# SmartCellPrototype.net
KiCad netlist of a schematic drawn in EAGLE
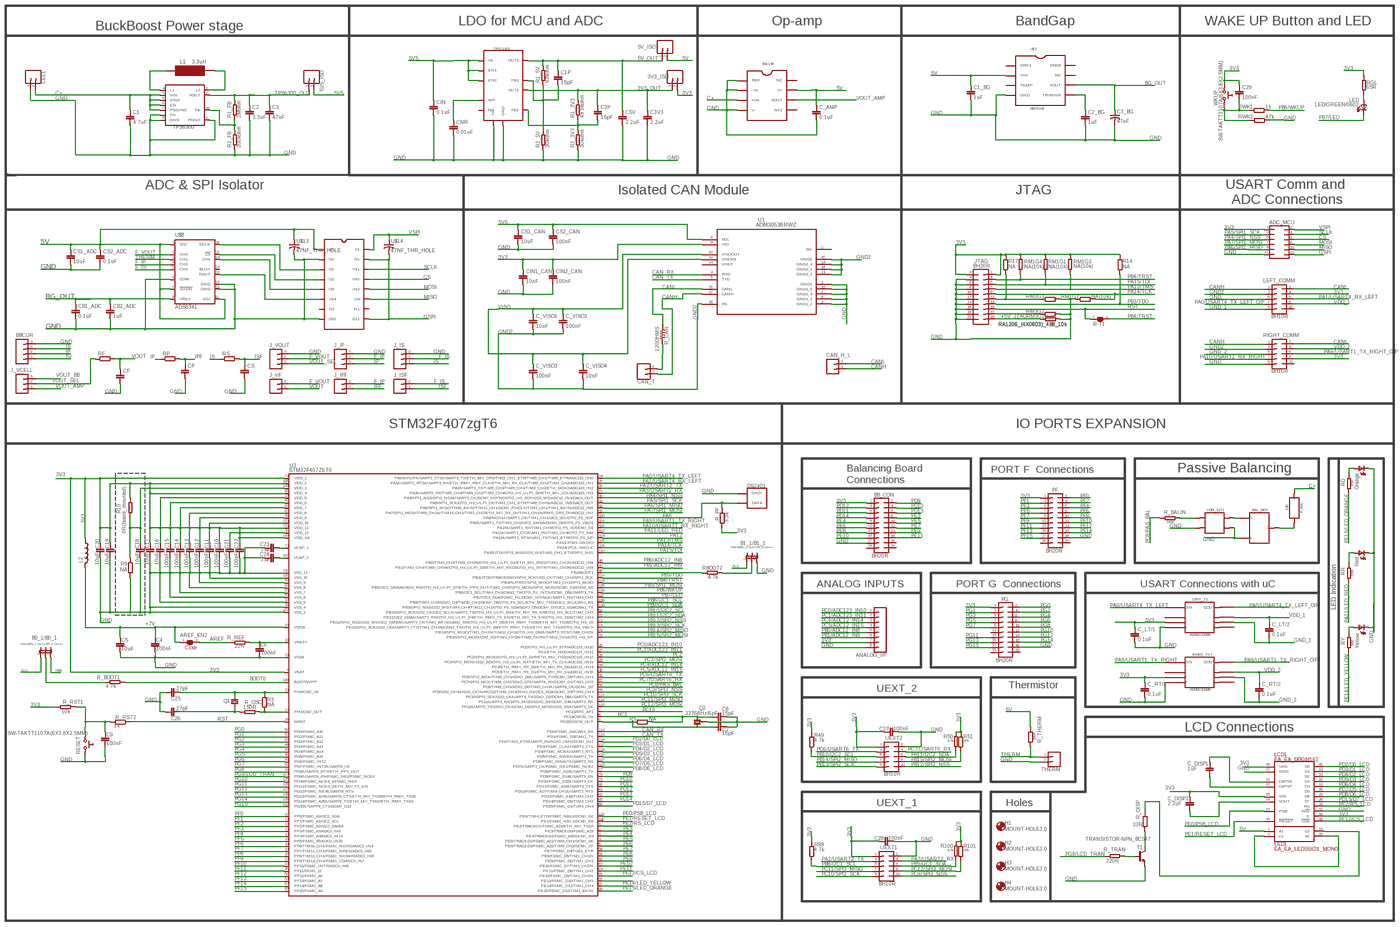
[diagram p0: schematic, sheet 1, overview]
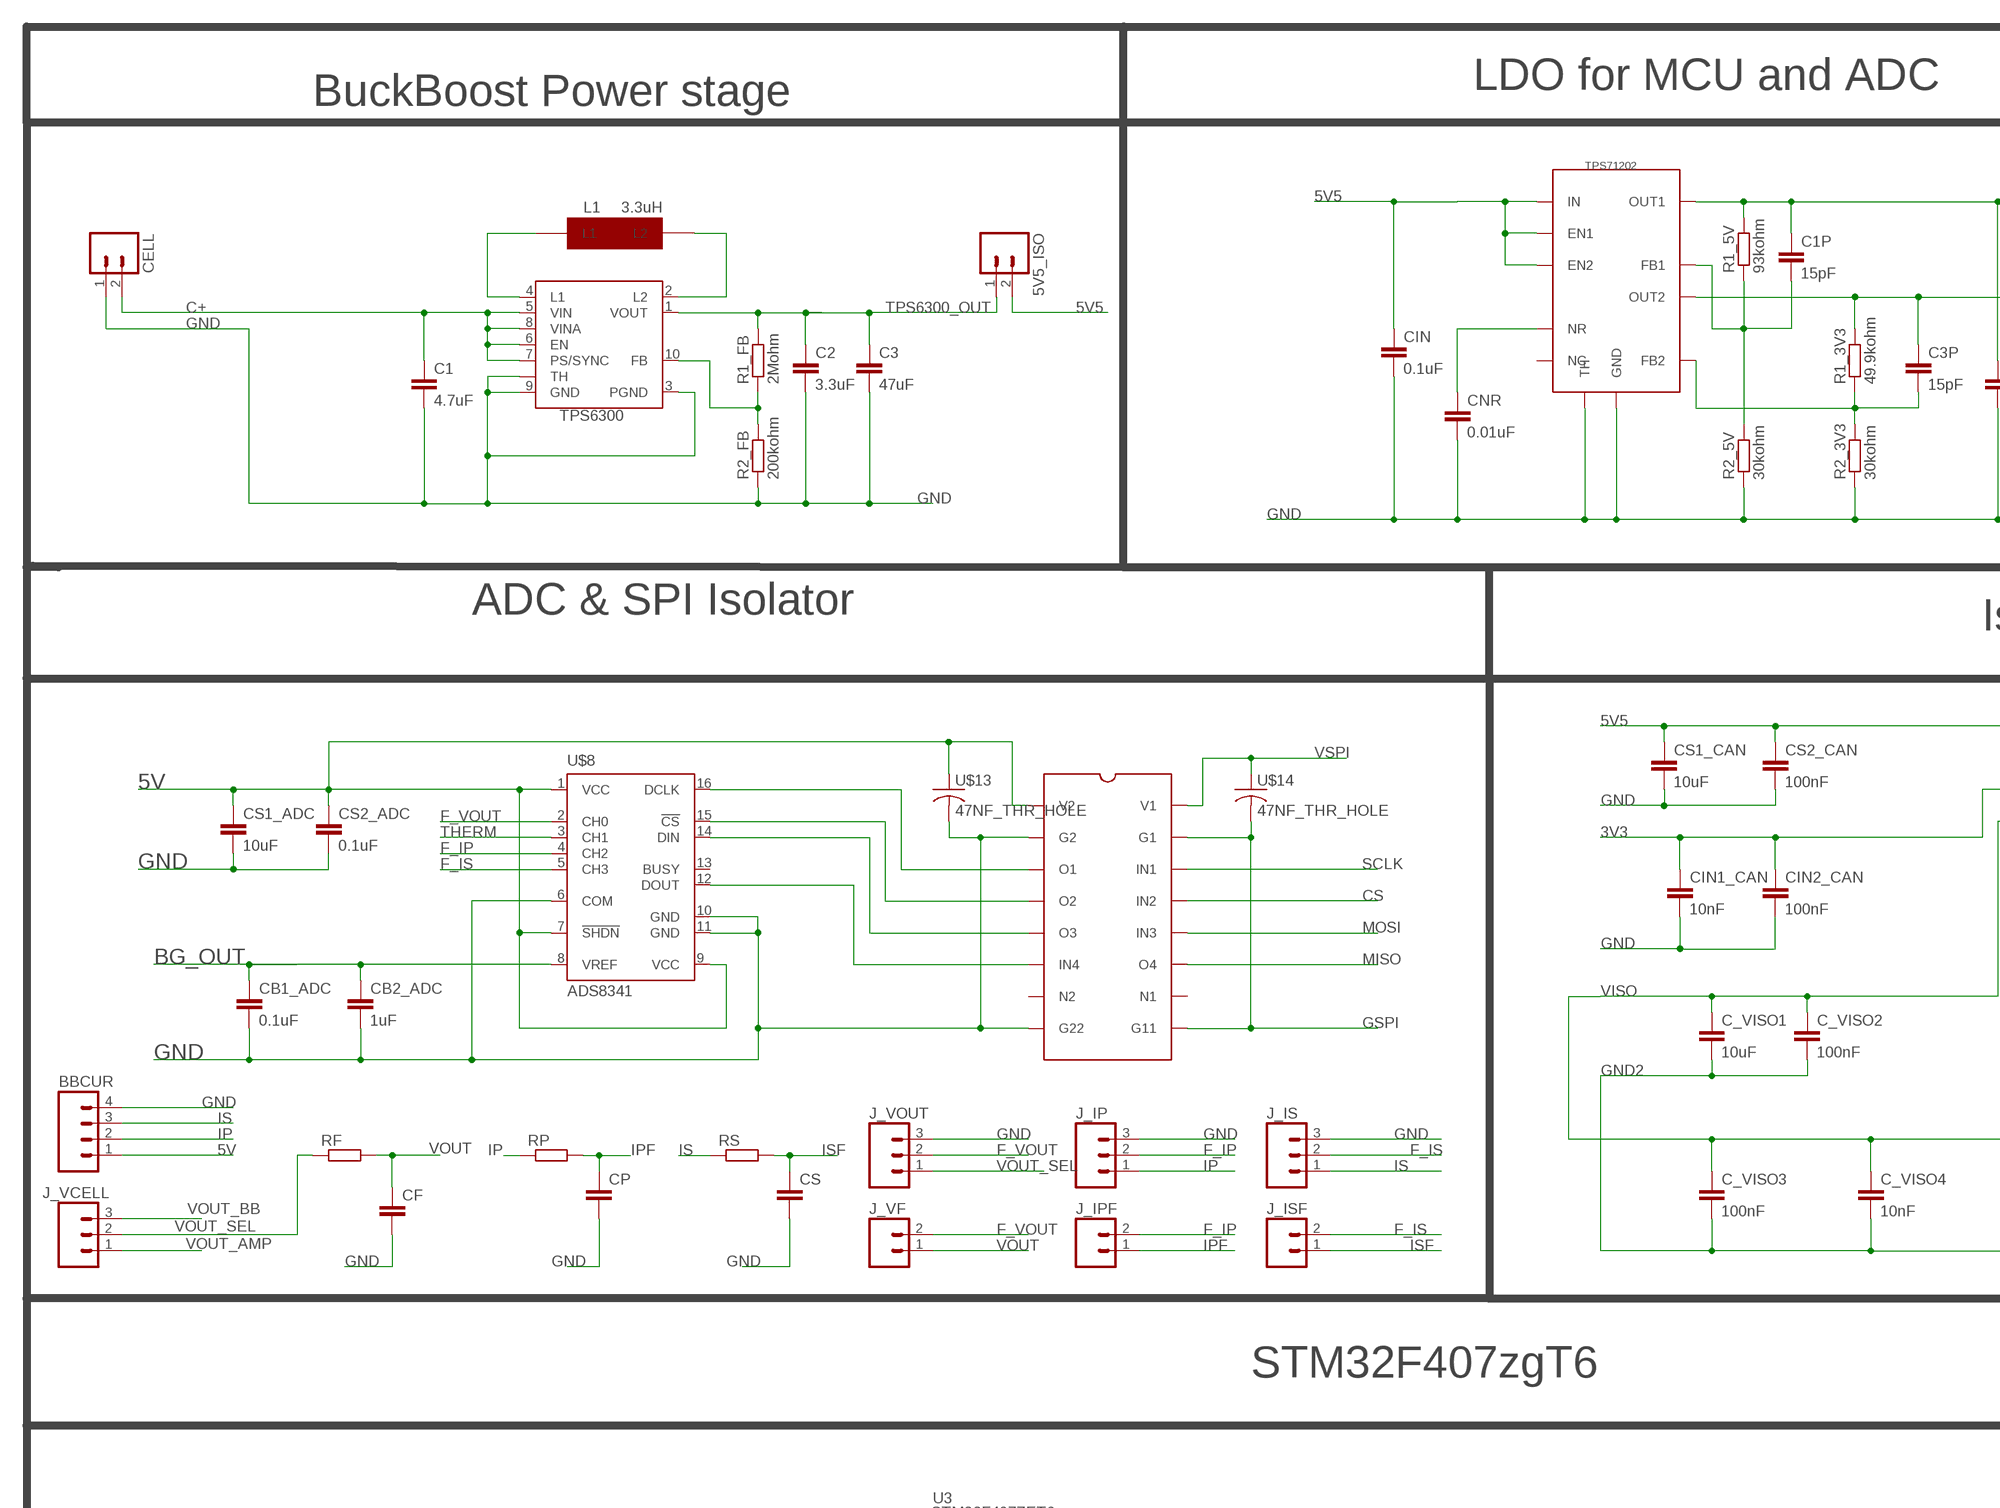
[diagram p1: schematic, sheet 1, part 1 of 4]
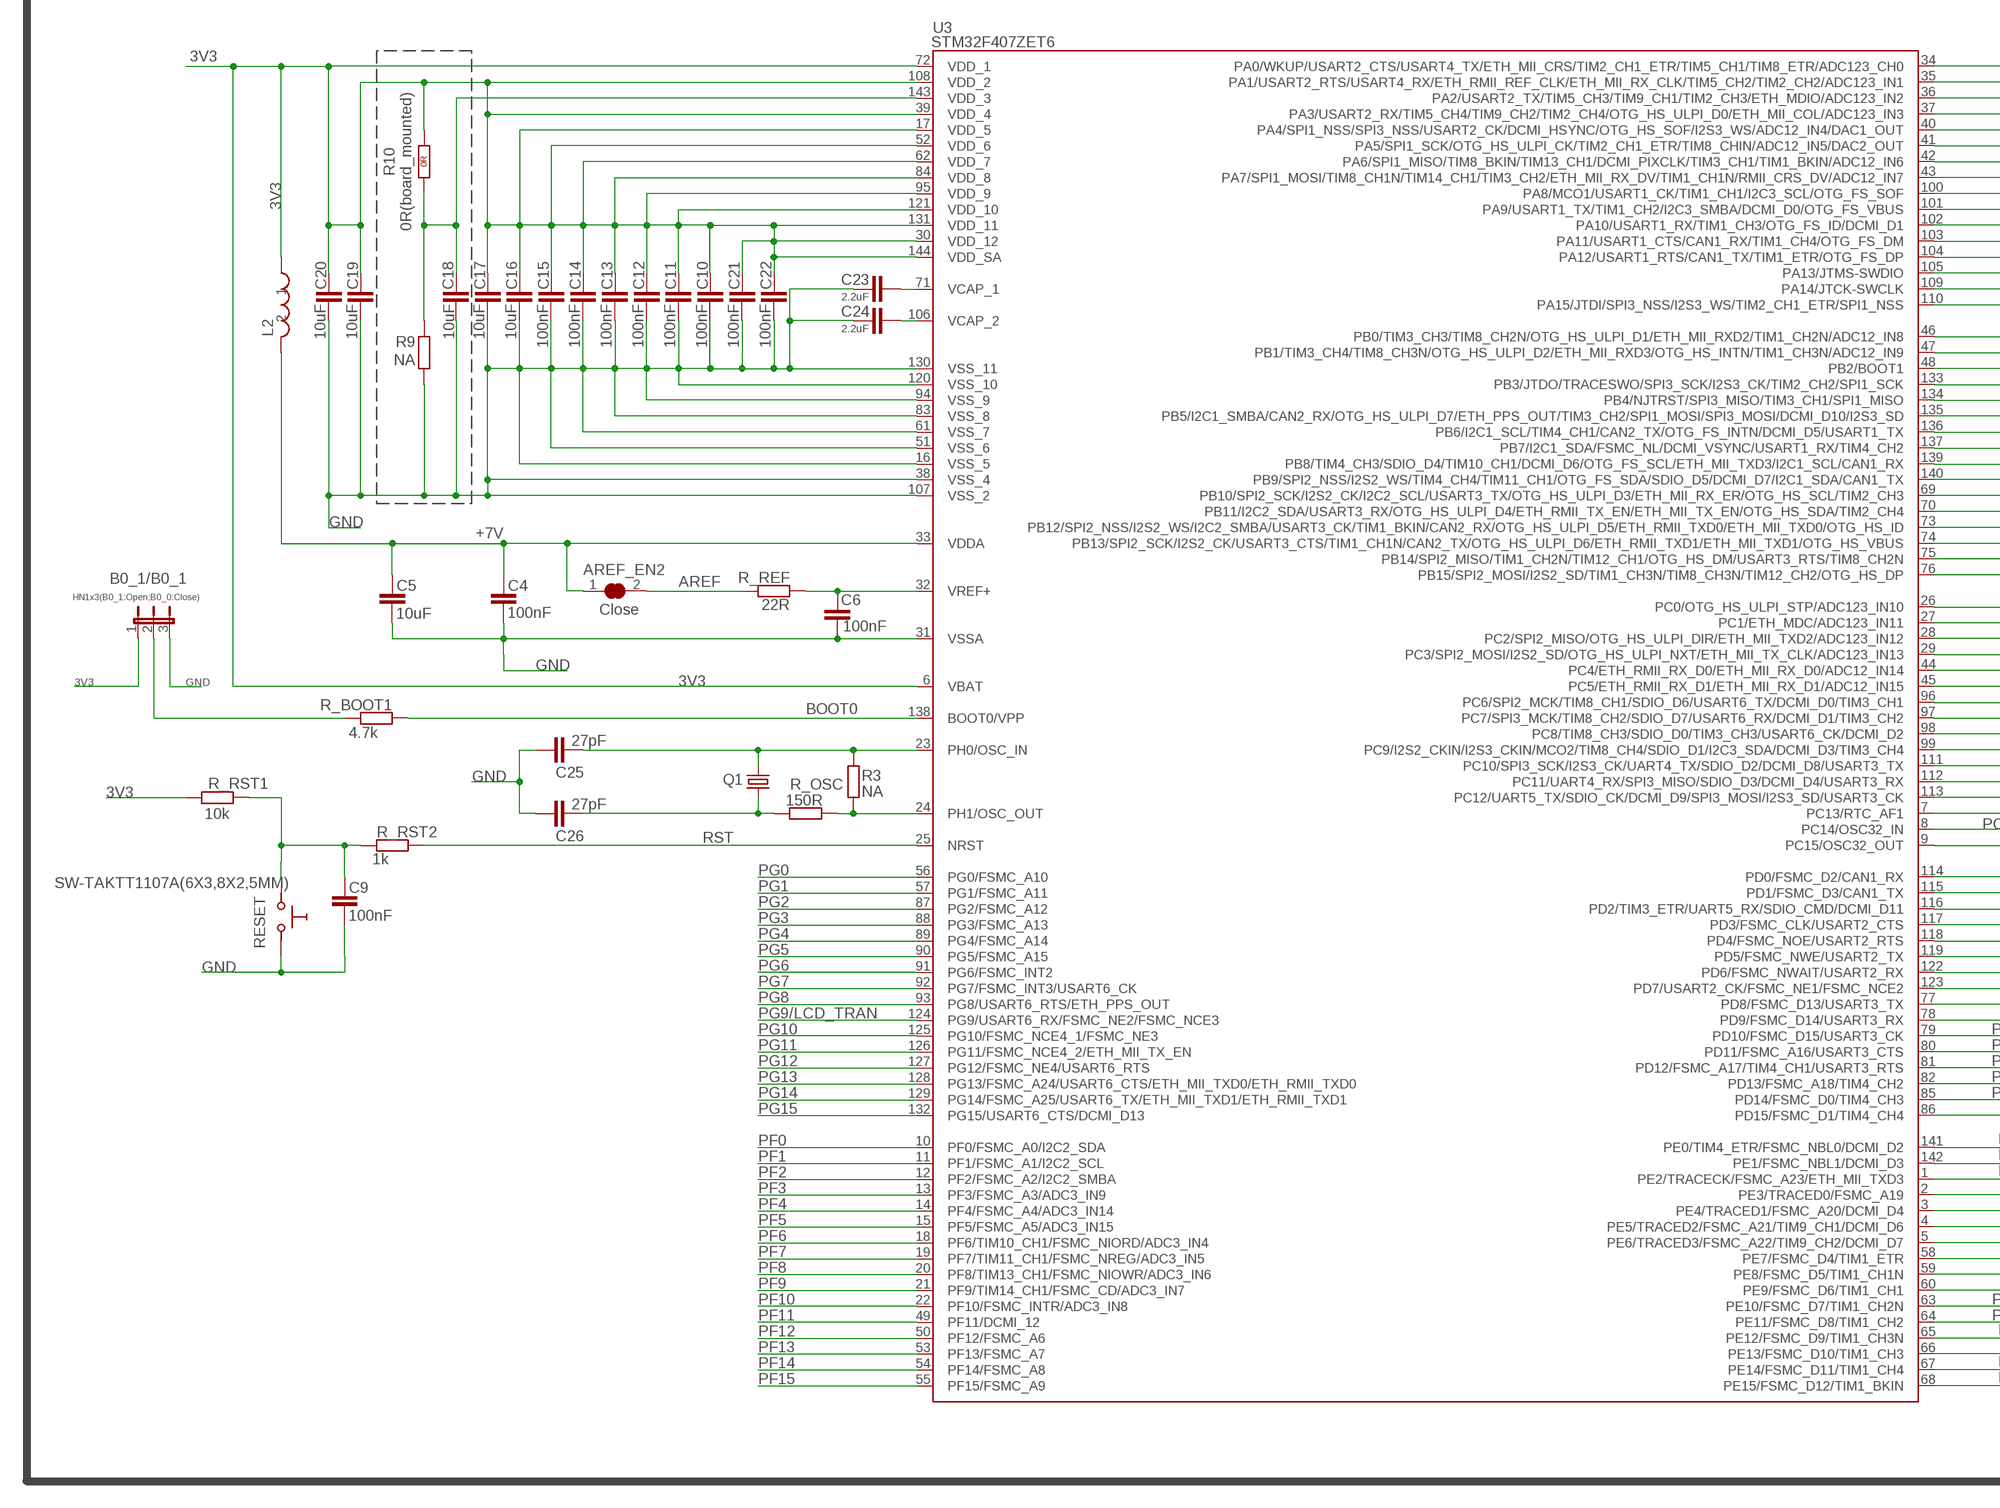
[diagram p2: schematic, sheet 1, part 2 of 4]
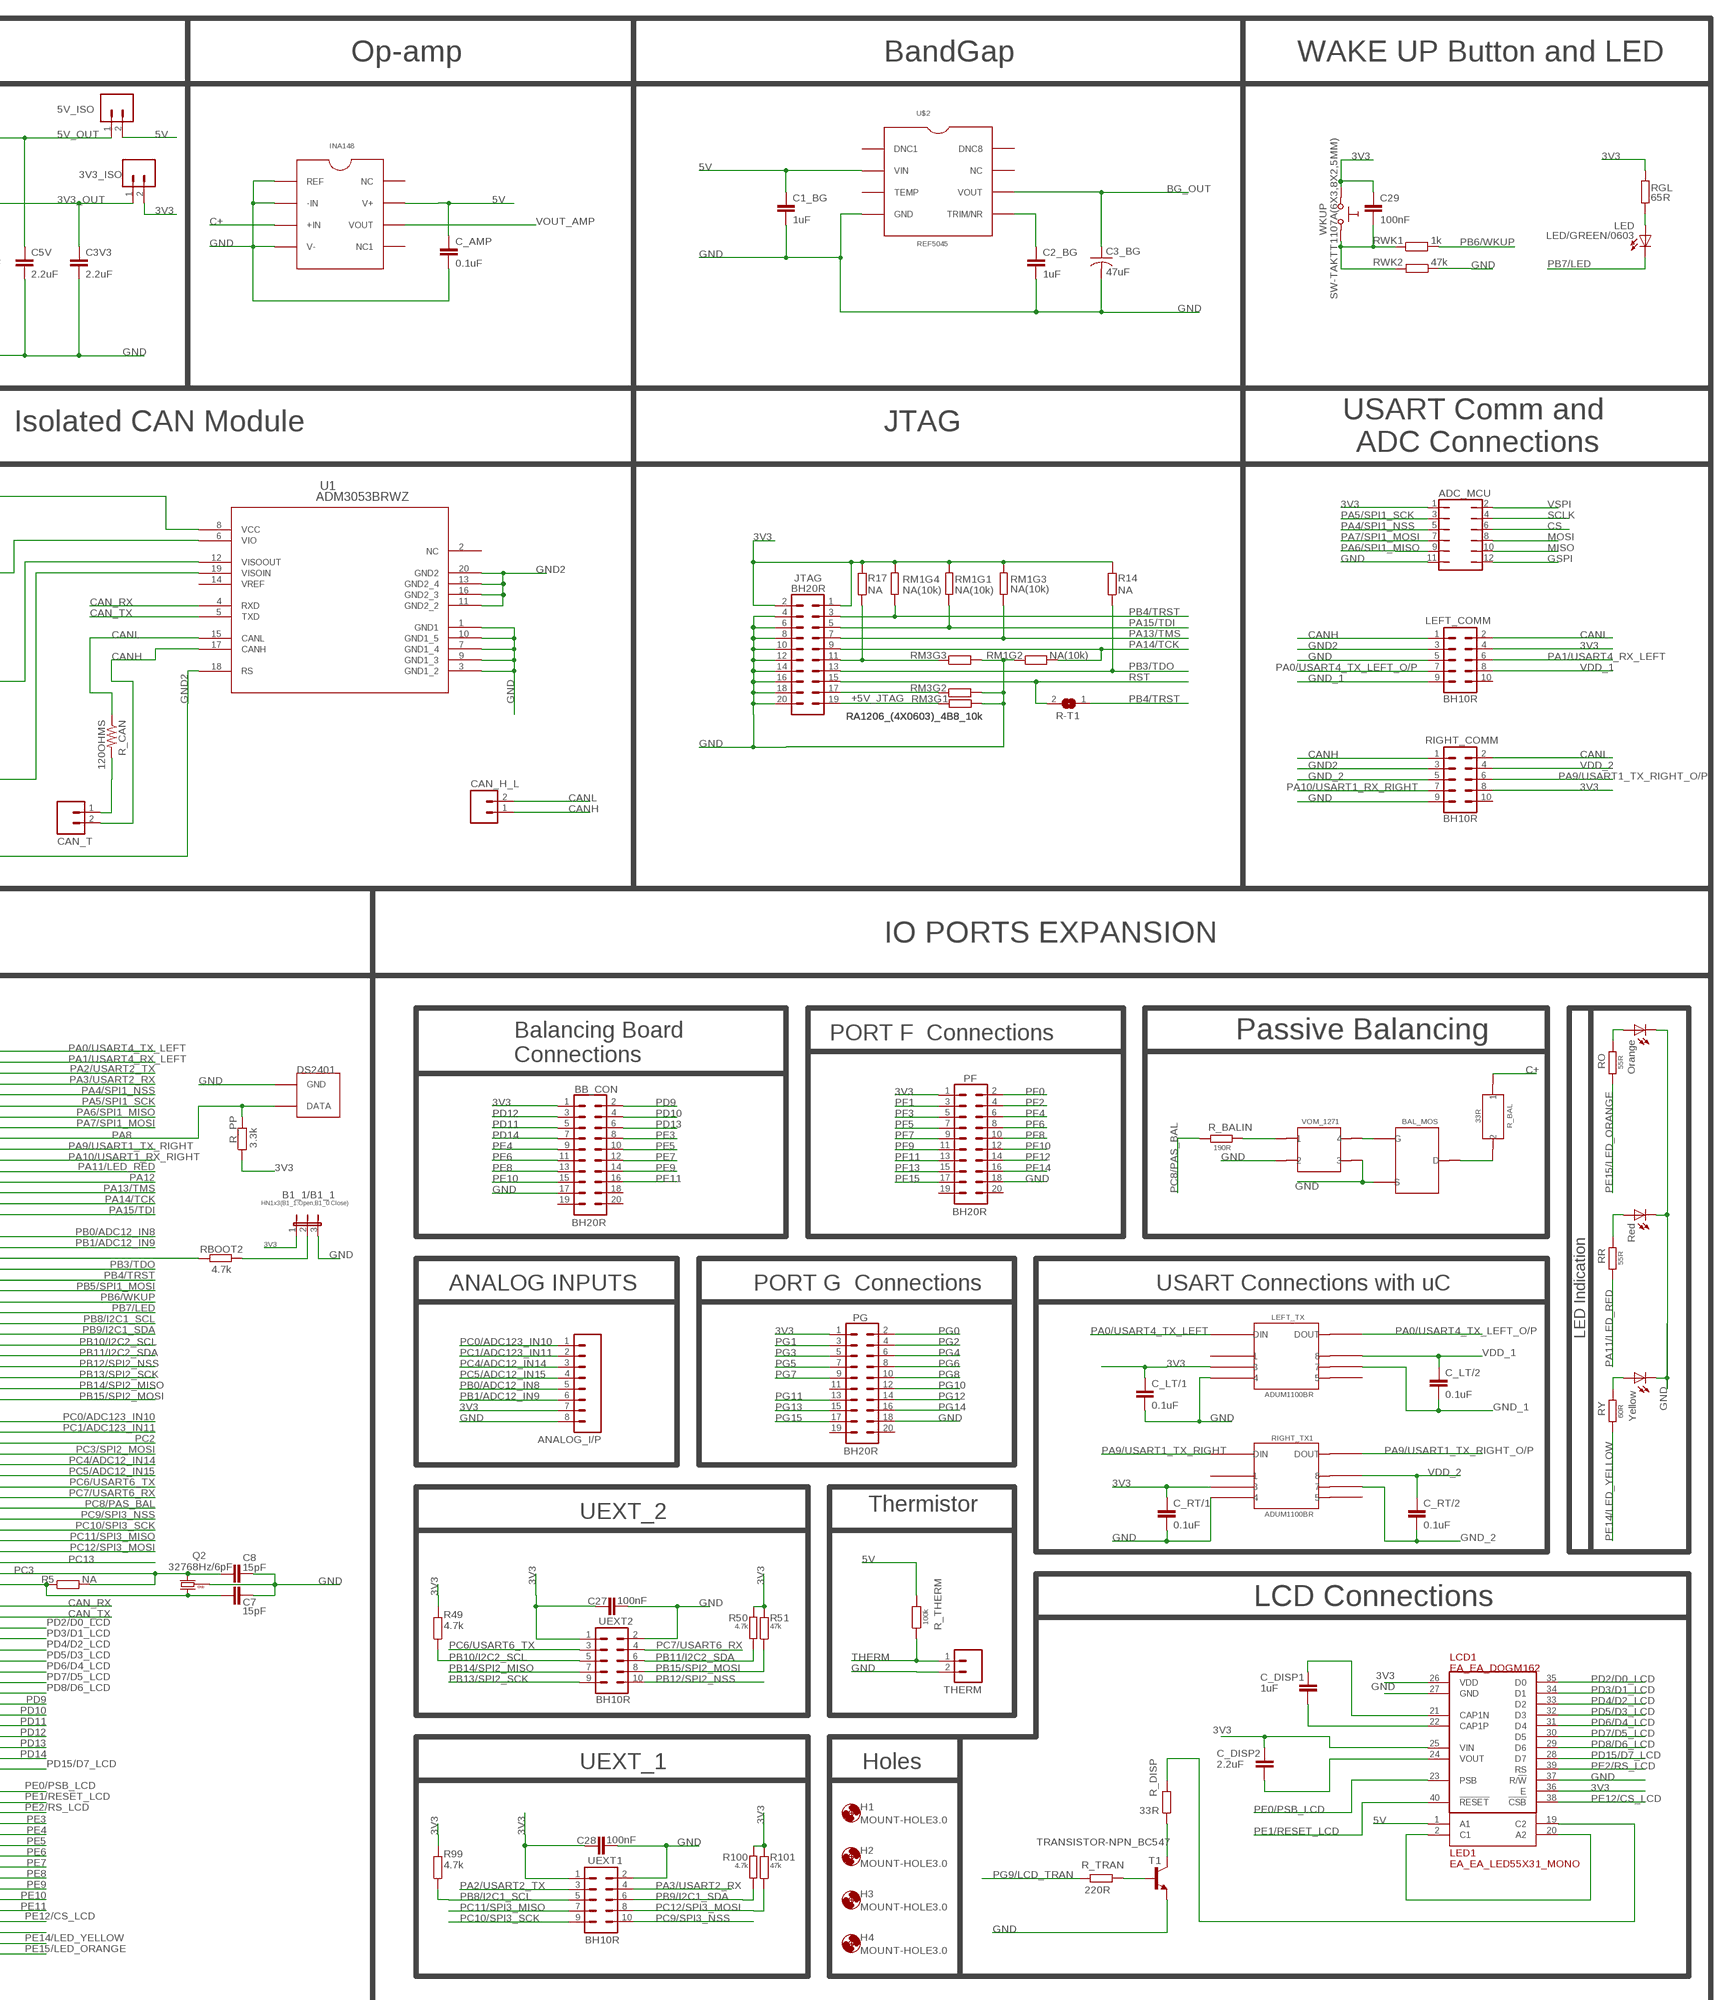
[diagram p3: schematic, sheet 1, part 3 of 4]
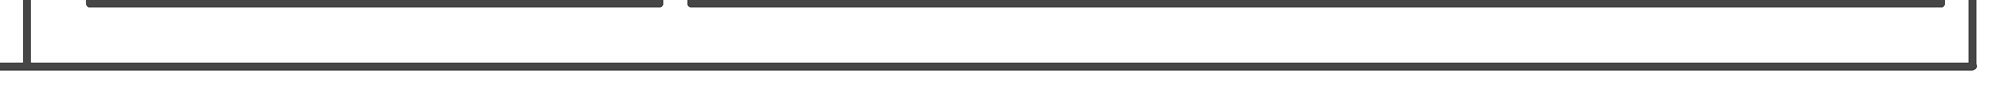
[diagram p4: schematic, sheet 1, part 4 of 4]

(export (version "E")
  (design (tool "Eeschema 10.0.6"))
  (components
    (comp (ref "3V3_ISO")
      (value "M02PTH")
      (footprint "eagle-import:1X02")
      (libsource (lib "eagle-import") (part "M02PTH"))
    )
    (comp (ref "5V5_ISO")
      (value "M02PTH")
      (footprint "eagle-import:1X02")
      (libsource (lib "eagle-import") (part "M02PTH"))
    )
    (comp (ref "5V_ISO")
      (value "M02PTH")
      (footprint "eagle-import:1X02")
      (libsource (lib "eagle-import") (part "M02PTH"))
    )
    (comp (ref "ADC_MCU")
      (value "JP6Q")
      (footprint "eagle-import:JP6Q")
      (libsource (lib "eagle-import") (part "JP6Q"))
    )
    (comp (ref "ANALOG_I/P")
      (value "M081X08")
      (footprint "eagle-import:1X08")
      (libsource (lib "eagle-import") (part "M081X08"))
    )
    (comp (ref "AREF_EN2")
      (value "Close")
      (footprint "eagle-import:SJ_1_SMALLER_CLOSE")
      (libsource (lib "eagle-import") (part "SJSJ_1_SMALLER_CLOSE"))
    )
    (comp (ref "B0_1/B0_1")
      (value "HN1x3(B0_1:Open;B0_0:Close)")
      (footprint "eagle-import:JP2")
      (libsource (lib "eagle-import") (part "JP2E"))
    )
    (comp (ref "B1_1/B1_1")
      (value "HN1x3(B1_1:Open;B1_0:Close)")
      (footprint "eagle-import:JP2")
      (libsource (lib "eagle-import") (part "JP2E"))
    )
    (comp (ref "BAL_MOS")
      (value "BAL_MOS")
      (footprint "eagle-import:BAL_MOS")
      (libsource (lib "eagle-import") (part "BAL_MOS"))
    )
    (comp (ref "BBCUR")
      (value "M04PTH")
      (footprint "eagle-import:1X04")
      (libsource (lib "eagle-import") (part "M04PTH"))
    )
    (comp (ref "BB_CON")
      (value "BH20R")
      (footprint "eagle-import:BH20R")
      (libsource (lib "eagle-import") (part "ML20R"))
    )
    (comp (ref "C1")
      (value "4.7uF")
      (footprint "eagle-import:C0603")
      (libsource (lib "eagle-import") (part "C-EUC0603"))
    )
    (comp (ref "C1P")
      (value "15pF")
      (footprint "eagle-import:C0603")
      (libsource (lib "eagle-import") (part "C-EUC0603"))
    )
    (comp (ref "C1_BG")
      (value "1uF")
      (footprint "eagle-import:C0603")
      (libsource (lib "eagle-import") (part "C-EUC0603"))
    )
    (comp (ref "C2")
      (value "3.3uF")
      (footprint "eagle-import:C0603")
      (libsource (lib "eagle-import") (part "C-EUC0603"))
    )
    (comp (ref "C2_BG")
      (value "1uF")
      (footprint "eagle-import:C0603")
      (libsource (lib "eagle-import") (part "C-EUC0603"))
    )
    (comp (ref "C3")
      (value "47uF")
      (footprint "eagle-import:C0805")
      (libsource (lib "eagle-import") (part "C-EUC0805"))
    )
    (comp (ref "C3P")
      (value "15pF")
      (footprint "eagle-import:C0603")
      (libsource (lib "eagle-import") (part "C-EUC0603"))
    )
    (comp (ref "C3V3")
      (value "2.2uF")
      (footprint "eagle-import:C0603")
      (libsource (lib "eagle-import") (part "C-EUC0603"))
    )
    (comp (ref "C3_BG")
      (value "47uF")
      (footprint "eagle-import:C3_BG")
      (libsource (lib "eagle-import") (part "C3_BG"))
    )
    (comp (ref "C4")
      (value "100nF")
      (footprint "eagle-import:C0603")
      (libsource (lib "eagle-import") (part "C-EUC0603"))
    )
    (comp (ref "C5")
      (value "10uF")
      (footprint "eagle-import:C0603")
      (libsource (lib "eagle-import") (part "C-EUC0603"))
    )
    (comp (ref "C5V")
      (value "2.2uF")
      (footprint "eagle-import:C0603")
      (libsource (lib "eagle-import") (part "C-EUC0603"))
    )
    (comp (ref "C6")
      (value "100nF")
      (footprint "eagle-import:C0603")
      (libsource (lib "eagle-import") (part "C-EUC0603"))
    )
    (comp (ref "C7")
      (value "15pF")
      (footprint "eagle-import:C0603")
      (libsource (lib "eagle-import") (part "C-EUC0603"))
    )
    (comp (ref "C8")
      (value "15pF")
      (footprint "eagle-import:C0603")
      (libsource (lib "eagle-import") (part "C-EUC0603"))
    )
    (comp (ref "C9")
      (value "100nF")
      (footprint "eagle-import:C0603")
      (libsource (lib "eagle-import") (part "C-EUC0603"))
    )
    (comp (ref "C10")
      (value "100nF")
      (footprint "eagle-import:C0603")
      (libsource (lib "eagle-import") (part "C-EUC0603"))
    )
    (comp (ref "C11")
      (value "100nF")
      (footprint "eagle-import:C0603")
      (libsource (lib "eagle-import") (part "C-EUC0603"))
    )
    (comp (ref "C12")
      (value "100nF")
      (footprint "eagle-import:C0603")
      (libsource (lib "eagle-import") (part "C-EUC0603"))
    )
    (comp (ref "C13")
      (value "100nF")
      (footprint "eagle-import:C0603")
      (libsource (lib "eagle-import") (part "C-EUC0603"))
    )
    (comp (ref "C14")
      (value "100nF")
      (footprint "eagle-import:C0603")
      (libsource (lib "eagle-import") (part "C-EUC0603"))
    )
    (comp (ref "C15")
      (value "100nF")
      (footprint "eagle-import:C0603")
      (libsource (lib "eagle-import") (part "C-EUC0603"))
    )
    (comp (ref "C16")
      (value "10uF")
      (footprint "eagle-import:C0603")
      (libsource (lib "eagle-import") (part "C-EUC0603"))
    )
    (comp (ref "C17")
      (value "10uF")
      (footprint "eagle-import:C0603")
      (libsource (lib "eagle-import") (part "C-EUC0603"))
    )
    (comp (ref "C18")
      (value "10uF")
      (footprint "eagle-import:C0603")
      (libsource (lib "eagle-import") (part "C-EUC0603"))
    )
    (comp (ref "C19")
      (value "10uF")
      (footprint "eagle-import:C0603")
      (libsource (lib "eagle-import") (part "C-EUC0603"))
    )
    (comp (ref "C20")
      (value "10uF")
      (footprint "eagle-import:C0603")
      (libsource (lib "eagle-import") (part "C-EUC0603"))
    )
    (comp (ref "C21")
      (value "100nF")
      (footprint "eagle-import:C0603")
      (libsource (lib "eagle-import") (part "C-EUC0603"))
    )
    (comp (ref "C22")
      (value "100nF")
      (footprint "eagle-import:C0603")
      (libsource (lib "eagle-import") (part "C-EUC0603"))
    )
    (comp (ref "C23")
      (value "2.2uF")
      (footprint "eagle-import:C0603")
      (libsource (lib "eagle-import") (part "C-EUC0603"))
    )
    (comp (ref "C24")
      (value "2.2uF")
      (footprint "eagle-import:C0603")
      (libsource (lib "eagle-import") (part "C-EUC0603"))
    )
    (comp (ref "C25")
      (value "27pF")
      (footprint "eagle-import:C0603")
      (libsource (lib "eagle-import") (part "C-EUC0603"))
    )
    (comp (ref "C26")
      (value "27pF")
      (footprint "eagle-import:C0603")
      (libsource (lib "eagle-import") (part "C-EUC0603"))
    )
    (comp (ref "C27")
      (value "100nF")
      (footprint "eagle-import:C0603")
      (libsource (lib "eagle-import") (part "C-EUC0603"))
    )
    (comp (ref "C28")
      (value "100nF")
      (footprint "eagle-import:C0603")
      (libsource (lib "eagle-import") (part "C-EUC0603"))
    )
    (comp (ref "C29")
      (value "100nF")
      (footprint "eagle-import:C0805")
      (libsource (lib "eagle-import") (part "C-EUC0805"))
    )
    (comp (ref "CAN_H_L")
      (value "M02PTH")
      (footprint "eagle-import:1X02")
      (libsource (lib "eagle-import") (part "M02PTH"))
    )
    (comp (ref "CAN_T")
      (value "M02PTH")
      (footprint "eagle-import:1X02")
      (libsource (lib "eagle-import") (part "M02PTH"))
    )
    (comp (ref "CB1_ADC")
      (value "0.1uF")
      (footprint "eagle-import:C0603")
      (libsource (lib "eagle-import") (part "C-EUC0603"))
    )
    (comp (ref "CB2_ADC")
      (value "1uF")
      (footprint "eagle-import:C0603")
      (libsource (lib "eagle-import") (part "C-EUC0603"))
    )
    (comp (ref "CELL")
      (value "M023.5MM")
      (footprint "eagle-import:SCREWTERMINAL-3.5MM-2")
      (libsource (lib "eagle-import") (part "M023.5MM"))
    )
    (comp (ref "CF")
      (value "C-EUC0603")
      (footprint "eagle-import:C0603")
      (libsource (lib "eagle-import") (part "C-EUC0603"))
    )
    (comp (ref "CIN")
      (value "0.1uF")
      (footprint "eagle-import:C0603")
      (libsource (lib "eagle-import") (part "C-EUC0603"))
    )
    (comp (ref "CIN1_CAN")
      (value "10nF")
      (footprint "eagle-import:C0603")
      (libsource (lib "eagle-import") (part "C-EUC0603"))
    )
    (comp (ref "CIN2_CAN")
      (value "100nF")
      (footprint "eagle-import:C0603")
      (libsource (lib "eagle-import") (part "C-EUC0603"))
    )
    (comp (ref "CNR")
      (value "0.01uF")
      (footprint "eagle-import:C0603")
      (libsource (lib "eagle-import") (part "C-EUC0603"))
    )
    (comp (ref "CP")
      (value "C-EUC0603")
      (footprint "eagle-import:C0603")
      (libsource (lib "eagle-import") (part "C-EUC0603"))
    )
    (comp (ref "CS")
      (value "C-EUC0603")
      (footprint "eagle-import:C0603")
      (libsource (lib "eagle-import") (part "C-EUC0603"))
    )
    (comp (ref "CS1_ADC")
      (value "10uF")
      (footprint "eagle-import:C0603")
      (libsource (lib "eagle-import") (part "C-EUC0603"))
    )
    (comp (ref "CS1_CAN")
      (value "10uF")
      (footprint "eagle-import:C0603")
      (libsource (lib "eagle-import") (part "C-EUC0603"))
    )
    (comp (ref "CS2_ADC")
      (value "0.1uF")
      (footprint "eagle-import:C0603")
      (libsource (lib "eagle-import") (part "C-EUC0603"))
    )
    (comp (ref "CS2_CAN")
      (value "100nF")
      (footprint "eagle-import:C0603")
      (libsource (lib "eagle-import") (part "C-EUC0603"))
    )
    (comp (ref "C_AMP")
      (value "0.1uF")
      (footprint "eagle-import:C0603")
      (libsource (lib "eagle-import") (part "C-EUC0603"))
    )
    (comp (ref "C_DISP1")
      (value "1uF")
      (footprint "eagle-import:C0603")
      (libsource (lib "eagle-import") (part "C-EUC0603"))
    )
    (comp (ref "C_DISP2")
      (value "2.2uF")
      (footprint "eagle-import:C0603")
      (libsource (lib "eagle-import") (part "C-EUC0603"))
    )
    (comp (ref "C_LT/1")
      (value "0.1uF")
      (footprint "eagle-import:C0603")
      (libsource (lib "eagle-import") (part "C-EUC0603"))
    )
    (comp (ref "C_LT/2")
      (value "0.1uF")
      (footprint "eagle-import:C0603")
      (libsource (lib "eagle-import") (part "C-EUC0603"))
    )
    (comp (ref "C_RT/1")
      (value "0.1uF")
      (footprint "eagle-import:C0603")
      (libsource (lib "eagle-import") (part "C-EUC0603"))
    )
    (comp (ref "C_RT/2")
      (value "0.1uF")
      (footprint "eagle-import:C0603")
      (libsource (lib "eagle-import") (part "C-EUC0603"))
    )
    (comp (ref "C_VISO1")
      (value "10uF")
      (footprint "eagle-import:C0603")
      (libsource (lib "eagle-import") (part "C-EUC0603"))
    )
    (comp (ref "C_VISO2")
      (value "100nF")
      (footprint "eagle-import:C0603")
      (libsource (lib "eagle-import") (part "C-EUC0603"))
    )
    (comp (ref "C_VISO3")
      (value "100nF")
      (footprint "eagle-import:C0603")
      (libsource (lib "eagle-import") (part "C-EUC0603"))
    )
    (comp (ref "C_VISO4")
      (value "10nF")
      (footprint "eagle-import:C0603")
      (libsource (lib "eagle-import") (part "C-EUC0603"))
    )
    (comp (ref "DS2401")
      (value "DS2401")
      (footprint "eagle-import:DS2401")
      (libsource (lib "eagle-import") (part "DS2401"))
    )
    (comp (ref "H1")
      (value "MOUNT-HOLE3.0")
      (footprint "eagle-import:3,0")
      (libsource (lib "eagle-import") (part "MOUNT-HOLE3.0"))
    )
    (comp (ref "H2")
      (value "MOUNT-HOLE3.0")
      (footprint "eagle-import:3,0")
      (libsource (lib "eagle-import") (part "MOUNT-HOLE3.0"))
    )
    (comp (ref "H3")
      (value "MOUNT-HOLE3.0")
      (footprint "eagle-import:3,0")
      (libsource (lib "eagle-import") (part "MOUNT-HOLE3.0"))
    )
    (comp (ref "H4")
      (value "MOUNT-HOLE3.0")
      (footprint "eagle-import:3,0")
      (libsource (lib "eagle-import") (part "MOUNT-HOLE3.0"))
    )
    (comp (ref "HCPL092J-00E")
      (value "HCPL902")
      (footprint "eagle-import:HCPL902")
      (libsource (lib "eagle-import") (part "HCPL902"))
    )
    (comp (ref "IC1")
      (value "TPS6300")
      (footprint "eagle-import:DRC-S-PVSON-N10")
      (fields (field (name "MPN") "TPS63000DRCTG4"))
      (libsource (lib "eagle-import") (part "TPS6300"))
    )
    (comp (ref "INA148")
      (value "INA148")
      (footprint "eagle-import:INA148")
      (libsource (lib "eagle-import") (part "INA148"))
    )
    (comp (ref "JTAG")
      (value "BH20R")
      (footprint "eagle-import:BH20R")
      (libsource (lib "eagle-import") (part "ML20R"))
    )
    (comp (ref "J_IP")
      (value "M03PTH")
      (footprint "eagle-import:1X03")
      (libsource (lib "eagle-import") (part "M03PTH"))
    )
    (comp (ref "J_IPF")
      (value "M02PTH")
      (footprint "eagle-import:1X02")
      (libsource (lib "eagle-import") (part "M02PTH"))
    )
    (comp (ref "J_IS")
      (value "M03PTH")
      (footprint "eagle-import:1X03")
      (libsource (lib "eagle-import") (part "M03PTH"))
    )
    (comp (ref "J_ISF")
      (value "M02PTH")
      (footprint "eagle-import:1X02")
      (libsource (lib "eagle-import") (part "M02PTH"))
    )
    (comp (ref "J_VCELL")
      (value "M03PTH")
      (footprint "eagle-import:1X03")
      (libsource (lib "eagle-import") (part "M03PTH"))
    )
    (comp (ref "J_VF")
      (value "M02PTH")
      (footprint "eagle-import:1X02")
      (libsource (lib "eagle-import") (part "M02PTH"))
    )
    (comp (ref "J_VOUT")
      (value "M03PTH")
      (footprint "eagle-import:1X03")
      (libsource (lib "eagle-import") (part "M03PTH"))
    )
    (comp (ref "L1")
      (value "3.3uH")
      (footprint "eagle-import:IND_COILCRAFT3.3UH")
      (libsource (lib "eagle-import") (part "IND_COILCRAFT3.3UH"))
    )
    (comp (ref "L2")
      (value "FERRITE_BEAD")
      (footprint "eagle-import:FERRITE_BEAD")
      (libsource (lib "eagle-import") (part "FERRITE_BEAD"))
    )
    (comp (ref "LCD1")
      (value "EA_EA_DOGM162")
      (footprint "eagle-import:EA_EA_DOGM")
      (libsource (lib "eagle-import") (part "EA_EA_DOGM162"))
    )
    (comp (ref "LED")
      (value "LED/GREEN/0603")
      (footprint "eagle-import:LED-0603")
      (libsource (lib "eagle-import") (part "LED0603DWS"))
    )
    (comp (ref "LED1")
      (value "EA_EA_LED55X31_MONO")
      (footprint "eagle-import:EA_EA_LED55X31")
      (libsource (lib "eagle-import") (part "EA_EA_LED55X31_MONO"))
    )
    (comp (ref "LEFT_COMM")
      (value "BH10R")
      (footprint "eagle-import:BH10R")
      (libsource (lib "eagle-import") (part "ML10R"))
    )
    (comp (ref "LEFT_TX")
      (value "ADUM1100BR")
      (footprint "eagle-import:R_8")
      (libsource (lib "eagle-import") (part "ADUM1100BR"))
    )
    (comp (ref "PF")
      (value "BH20R")
      (footprint "eagle-import:BH20R")
      (libsource (lib "eagle-import") (part "ML20R"))
    )
    (comp (ref "PG")
      (value "BH20R")
      (footprint "eagle-import:BH20R")
      (libsource (lib "eagle-import") (part "ML20R"))
    )
    (comp (ref "Q1")
      (value "HC49/S2")
      (footprint "eagle-import:HC49_SMD2")
      (libsource (lib "eagle-import") (part "HC49/S2"))
    )
    (comp (ref "Q2")
      (value "32768Hz/6pF")
      (footprint "eagle-import:TC26H_3_REPAIR_SMD")
      (libsource (lib "eagle-import") (part "Q_GND1"))
    )
    (comp (ref "R-T1")
      (value "Open")
      (footprint "eagle-import:SJ_1_SMALLER")
      (libsource (lib "eagle-import") (part "SJSJ_SMALLER"))
    )
    (comp (ref "R1_3V3")
      (value "49.9kohm")
      (footprint "eagle-import:R0603")
      (libsource (lib "eagle-import") (part "R-EU_R0603"))
    )
    (comp (ref "R1_5V")
      (value "93kohm")
      (footprint "eagle-import:R0603")
      (libsource (lib "eagle-import") (part "R-EU_R0603"))
    )
    (comp (ref "R1_FB")
      (value "2Mohm")
      (footprint "eagle-import:R0603")
      (libsource (lib "eagle-import") (part "R-EU_R0603"))
    )
    (comp (ref "R2_3V3")
      (value "30kohm")
      (footprint "eagle-import:R0603")
      (libsource (lib "eagle-import") (part "R-EU_R0603"))
    )
    (comp (ref "R2_5V")
      (value "30kohm")
      (footprint "eagle-import:R0603")
      (libsource (lib "eagle-import") (part "R-EU_R0603"))
    )
    (comp (ref "R2_FB")
      (value "200kohm")
      (footprint "eagle-import:R0603")
      (libsource (lib "eagle-import") (part "R-EU_R0603"))
    )
    (comp (ref "R3")
      (value "NA")
      (footprint "eagle-import:R0603")
      (libsource (lib "eagle-import") (part "R-EU_R0603"))
    )
    (comp (ref "R5")
      (value "NA")
      (footprint "eagle-import:R0603")
      (libsource (lib "eagle-import") (part "R-EU_R0603"))
    )
    (comp (ref "R9")
      (value "NA")
      (footprint "eagle-import:R0603")
      (libsource (lib "eagle-import") (part "R-EU_R0603"))
    )
    (comp (ref "R10")
      (value "0R(board_mounted)")
      (footprint "eagle-import:0603_0R")
      (libsource (lib "eagle-import") (part "R_0R0R(NA)"))
    )
    (comp (ref "R14")
      (value "NA")
      (footprint "eagle-import:R0603")
      (libsource (lib "eagle-import") (part "R-EU_R0603"))
    )
    (comp (ref "R17")
      (value "NA")
      (footprint "eagle-import:R0603")
      (libsource (lib "eagle-import") (part "R-EU_R0603"))
    )
    (comp (ref "R49")
      (value "4.7k")
      (footprint "eagle-import:R0603")
      (libsource (lib "eagle-import") (part "R-EU_R0603"))
    )
    (comp (ref "R50")
      (value "4.7k")
      (footprint "eagle-import:R0603")
      (libsource (lib "eagle-import") (part "R-EU_R0603"))
    )
    (comp (ref "R51")
      (value "47k")
      (footprint "eagle-import:R0603")
      (libsource (lib "eagle-import") (part "R-EU_R0603"))
    )
    (comp (ref "R99")
      (value "4.7k")
      (footprint "eagle-import:R0603")
      (libsource (lib "eagle-import") (part "R-EU_R0603"))
    )
    (comp (ref "R100")
      (value "4.7k")
      (footprint "eagle-import:R0603")
      (libsource (lib "eagle-import") (part "R-EU_R0603"))
    )
    (comp (ref "R101")
      (value "47k")
      (footprint "eagle-import:R0603")
      (libsource (lib "eagle-import") (part "R-EU_R0603"))
    )
    (comp (ref "RBOOT2")
      (value "4.7k")
      (footprint "eagle-import:R0603")
      (libsource (lib "eagle-import") (part "R-EU_R0603"))
    )
    (comp (ref "RESET")
      (value "SW-TAKTT1107A(6X3,8X2,5MM)")
      (footprint "eagle-import:WS-TAKT_6X3.5_SMD_NOCREAM")
      (libsource (lib "eagle-import") (part "SW-TAKTT1107A(6X3,8X2,5MM)"))
    )
    (comp (ref "RF")
      (value "R-EU_R0603")
      (footprint "eagle-import:R0603")
      (libsource (lib "eagle-import") (part "R-EU_R0603"))
    )
    (comp (ref "RGL")
      (value "65R")
      (footprint "eagle-import:R0603_5MIL_DWS")
      (libsource (lib "eagle-import") (part "R-EU_R0603_5MIL_DWS"))
    )
    (comp (ref "RIGHT_COMM")
      (value "BH10R")
      (footprint "eagle-import:BH10R")
      (libsource (lib "eagle-import") (part "ML10R"))
    )
    (comp (ref "RIGHT_TX1")
      (value "ADUM1100BR")
      (footprint "eagle-import:R_8")
      (libsource (lib "eagle-import") (part "ADUM1100BR"))
    )
    (comp (ref "RM1")
      (value "NA(10k)")
      (footprint "eagle-import:R_MATRIX_4")
      (libsource (lib "eagle-import") (part "R_MATRIX_4E"))
    )
    (comp (ref "RM3")
      (value "RA1206_(4X0603)_4B8_10k")
      (footprint "eagle-import:R_MATRIX_4")
      (libsource (lib "eagle-import") (part "R_MATRIX_4E"))
    )
    (comp (ref "RO")
      (value "55R")
      (footprint "eagle-import:R0603")
      (libsource (lib "eagle-import") (part "R-EU_R0603"))
    )
    (comp (ref "RP")
      (value "R-EU_R0603")
      (footprint "eagle-import:R0603")
      (libsource (lib "eagle-import") (part "R-EU_R0603"))
    )
    (comp (ref "RR")
      (value "55R")
      (footprint "eagle-import:R0603")
      (libsource (lib "eagle-import") (part "R-EU_R0603"))
    )
    (comp (ref "RS")
      (value "R-EU_R0603")
      (footprint "eagle-import:R0603")
      (libsource (lib "eagle-import") (part "R-EU_R0603"))
    )
    (comp (ref "RWK1")
      (value "1k")
      (footprint "eagle-import:R0603_5MIL_DWS")
      (libsource (lib "eagle-import") (part "R-EU_R0603_5MIL_DWS"))
    )
    (comp (ref "RWK2")
      (value "47k")
      (footprint "eagle-import:R0603_5MIL_DWS")
      (libsource (lib "eagle-import") (part "R-EU_R0603_5MIL_DWS"))
    )
    (comp (ref "RY")
      (value "60R")
      (footprint "eagle-import:R0603")
      (libsource (lib "eagle-import") (part "R-EU_R0603"))
    )
    (comp (ref "R_BAL")
      (value "33R")
      (footprint "eagle-import:R_BAL")
      (libsource (lib "eagle-import") (part "R_BAL"))
    )
    (comp (ref "R_BALIN")
      (value "190R")
      (footprint "eagle-import:R0603")
      (libsource (lib "eagle-import") (part "R-EU_R0603"))
    )
    (comp (ref "R_BOOT1")
      (value "4.7k")
      (footprint "eagle-import:R0603")
      (libsource (lib "eagle-import") (part "R-EU_R0603"))
    )
    (comp (ref "R_CAN")
      (value "120OHMS")
      (footprint "eagle-import:120OHM")
      (libsource (lib "eagle-import") (part "120OHMS"))
    )
    (comp (ref "R_DISP")
      (value "33R")
      (footprint "eagle-import:R0603")
      (libsource (lib "eagle-import") (part "R-EU_R0603"))
    )
    (comp (ref "R_OSC")
      (value "150R")
      (footprint "eagle-import:R0603")
      (libsource (lib "eagle-import") (part "R-EU_R0603"))
    )
    (comp (ref "R_PP")
      (value "3.3k")
      (footprint "eagle-import:R0603")
      (libsource (lib "eagle-import") (part "R-EU_R0603"))
    )
    (comp (ref "R_REF")
      (value "22R")
      (footprint "eagle-import:R0603")
      (libsource (lib "eagle-import") (part "R-EU_R0603"))
    )
    (comp (ref "R_RST1")
      (value "10k")
      (footprint "eagle-import:R0603")
      (libsource (lib "eagle-import") (part "R-EU_R0603"))
    )
    (comp (ref "R_RST2")
      (value "1k")
      (footprint "eagle-import:R0603")
      (libsource (lib "eagle-import") (part "R-EU_R0603"))
    )
    (comp (ref "R_THERM")
      (value "100k")
      (footprint "eagle-import:R0603")
      (libsource (lib "eagle-import") (part "R-EU_R0603"))
    )
    (comp (ref "R_TRAN")
      (value "220R")
      (footprint "eagle-import:R0603")
      (libsource (lib "eagle-import") (part "R-EU_R0603"))
    )
    (comp (ref "T1")
      (value "TRANSISTOR-NPN_BC547")
      (footprint "eagle-import:TRANSISTOR-NPN_TO92")
      (libsource (lib "eagle-import") (part "TRANSISTOR-NPN_BC547"))
    )
    (comp (ref "THERM")
      (value "M02JST-PTH-2")
      (footprint "eagle-import:JST-2-PTH")
      (libsource (lib "eagle-import") (part "M02JST-PTH-2"))
    )
    (comp (ref "U$1")
      (value "TPS71202")
      (footprint "eagle-import:TPS71202_LDO_ADC_MCU")
      (libsource (lib "eagle-import") (part "TPS71202"))
    )
    (comp (ref "U$2")
      (value "REF5045")
      (footprint "eagle-import:REF5045_BG")
      (libsource (lib "eagle-import") (part "REF5045"))
    )
    (comp (ref "U$3")
      (value "Yellow")
      (footprint "eagle-import:LED_0805")
      (libsource (lib "eagle-import") (part "LED_0805"))
    )
    (comp (ref "U$4")
      (value "Red")
      (footprint "eagle-import:LED_0805")
      (libsource (lib "eagle-import") (part "LED_0805"))
    )
    (comp (ref "U$5")
      (value "Orange")
      (footprint "eagle-import:LED_0805")
      (libsource (lib "eagle-import") (part "LED_0805"))
    )
    (comp (ref "U$8")
      (value "ADS8341")
      (footprint "eagle-import:ADS8341")
      (libsource (lib "eagle-import") (part "ADS8341"))
    )
    (comp (ref "U$13")
      (value "47NF_THR_HOLE")
      (footprint "eagle-import:47NF_THR_HOLE")
      (libsource (lib "eagle-import") (part "47NF_THR_HOLE"))
    )
    (comp (ref "U$14")
      (value "47NF_THR_HOLE")
      (footprint "eagle-import:47NF_THR_HOLE")
      (libsource (lib "eagle-import") (part "47NF_THR_HOLE"))
    )
    (comp (ref "U1")
      (value "ADM3053BRWZ")
      (footprint "eagle-import:RW_20")
      (libsource (lib "eagle-import") (part "ADM3053BRWZ"))
    )
    (comp (ref "U3")
      (value "STM32F407ZET6")
      (footprint "eagle-import:LQFP144")
      (libsource (lib "eagle-import") (part "STM32F207ZET6"))
    )
    (comp (ref "UEXT1")
      (value "BH10R")
      (footprint "eagle-import:BH10R")
      (libsource (lib "eagle-import") (part "ML10R"))
    )
    (comp (ref "UEXT2")
      (value "BH10R")
      (footprint "eagle-import:BH10R")
      (libsource (lib "eagle-import") (part "ML10R"))
    )
    (comp (ref "VOM_1271")
      (value "VOM1271")
      (footprint "eagle-import:VOM1271")
      (libsource (lib "eagle-import") (part "VOM1271"))
    )
    (comp (ref "WKUP")
      (value "SW-TAKTT1107A(6X3,8X2,5MM)")
      (footprint "eagle-import:WS-TAKT_6X3.5_SMD_NOCREAM")
      (libsource (lib "eagle-import") (part "SW-TAKTT1107A(6X3,8X2,5MM)"))
    )
  )
  (nets
    (net (code "1") (name "/+5V_JTAG") (class "Default")
      (node (ref "JTAG") (pin "19") (pinfunction "19_19") (pintype "passive"))
      (node (ref "RM3") (pin "1.1") (pinfunction "1_1.1") (pintype "passive"))
    )
    (net (code "2") (name "/+7V") (class "Default")
      (node (ref "AREF_EN2") (pin "1") (pinfunction "1_1") (pintype "passive"))
      (node (ref "C4") (pin "2") (pinfunction "2_2") (pintype "passive"))
      (node (ref "C5") (pin "1") (pinfunction "1_1") (pintype "passive"))
      (node (ref "L2") (pin "2") (pinfunction "2_2") (pintype "passive"))
      (node (ref "U3") (pin "33") (pinfunction "VDDA_33") (pintype "power_in"))
    )
    (net (code "3") (name "/3V3") (class "Default")
      (node (ref "3V3_ISO") (pin "2") (pinfunction "2_2") (pintype "passive"))
      (node (ref "ADC_MCU") (pin "1") (pinfunction "1_1") (pintype "passive"))
      (node (ref "ANALOG_I/P") (pin "7") (pinfunction "7_7") (pintype "passive"))
      (node (ref "B0_1/B0_1") (pin "1") (pinfunction "1_1") (pintype "passive"))
      (node (ref "B1_1/B1_1") (pin "1") (pinfunction "1_1") (pintype "passive"))
      (node (ref "BB_CON") (pin "1") (pinfunction "1_1") (pintype "passive"))
      (node (ref "C10") (pin "2") (pinfunction "2_2") (pintype "passive"))
      (node (ref "C11") (pin "2") (pinfunction "2_2") (pintype "passive"))
      (node (ref "C12") (pin "2") (pinfunction "2_2") (pintype "passive"))
      (node (ref "C13") (pin "2") (pinfunction "2_2") (pintype "passive"))
      (node (ref "C14") (pin "2") (pinfunction "2_2") (pintype "passive"))
      (node (ref "C15") (pin "2") (pinfunction "2_2") (pintype "passive"))
      (node (ref "C16") (pin "2") (pinfunction "2_2") (pintype "passive"))
      (node (ref "C17") (pin "2") (pinfunction "2_2") (pintype "passive"))
      (node (ref "C19") (pin "2") (pinfunction "2_2") (pintype "passive"))
      (node (ref "C20") (pin "2") (pinfunction "2_2") (pintype "passive"))
      (node (ref "C21") (pin "2") (pinfunction "2_2") (pintype "passive"))
      (node (ref "C22") (pin "2") (pinfunction "2_2") (pintype "passive"))
      (node (ref "C27") (pin "2") (pinfunction "2_2") (pintype "passive"))
      (node (ref "C28") (pin "2") (pinfunction "2_2") (pintype "passive"))
      (node (ref "C29") (pin "2") (pinfunction "2_2") (pintype "passive"))
      (node (ref "CIN1_CAN") (pin "1") (pinfunction "1_1") (pintype "passive"))
      (node (ref "CIN2_CAN") (pin "1") (pinfunction "1_1") (pintype "passive"))
      (node (ref "C_DISP2") (pin "1") (pinfunction "1_1") (pintype "passive"))
      (node (ref "C_LT/1") (pin "1") (pinfunction "1_1") (pintype "passive"))
      (node (ref "C_RT/1") (pin "1") (pinfunction "1_1") (pintype "passive"))
      (node (ref "JTAG") (pin "1") (pinfunction "1_1") (pintype "passive"))
      (node (ref "JTAG") (pin "2") (pinfunction "2_2") (pintype "passive"))
      (node (ref "L2") (pin "1") (pinfunction "1_1") (pintype "passive"))
      (node (ref "LCD1") (pin "25") (pinfunction "VIN_25") (pintype "passive"))
      (node (ref "LCD1") (pin "26") (pinfunction "VDD_26") (pintype "power_in"))
      (node (ref "LCD1") (pin "36") (pinfunction "E_36") (pintype "input"))
      (node (ref "LEFT_COMM") (pin "4") (pinfunction "4_4") (pintype "passive"))
      (node (ref "LEFT_TX") (pin "3") (pinfunction "3_3") (pintype "passive"))
      (node (ref "PF") (pin "1") (pinfunction "1_1") (pintype "passive"))
      (node (ref "PG") (pin "1") (pinfunction "1_1") (pintype "passive"))
      (node (ref "R10") (pin "2") (pinfunction "1.2_2") (pintype "passive"))
      (node (ref "R100") (pin "2") (pinfunction "2_2") (pintype "passive"))
      (node (ref "R101") (pin "2") (pinfunction "2_2") (pintype "passive"))
      (node (ref "R14") (pin "2") (pinfunction "2_2") (pintype "passive"))
      (node (ref "R17") (pin "2") (pinfunction "2_2") (pintype "passive"))
      (node (ref "R49") (pin "2") (pinfunction "2_2") (pintype "passive"))
      (node (ref "R50") (pin "2") (pinfunction "2_2") (pintype "passive"))
      (node (ref "R51") (pin "2") (pinfunction "2_2") (pintype "passive"))
      (node (ref "R99") (pin "2") (pinfunction "2_2") (pintype "passive"))
      (node (ref "RGL") (pin "2") (pinfunction "2_2") (pintype "passive"))
      (node (ref "RIGHT_COMM") (pin "8") (pinfunction "8_8") (pintype "passive"))
      (node (ref "RIGHT_TX1") (pin "3") (pinfunction "3_3") (pintype "passive"))
      (node (ref "RM1") (pin "1.2") (pinfunction "2_1.2") (pintype "passive"))
      (node (ref "RM1") (pin "3.2") (pinfunction "2_3.2") (pintype "passive"))
      (node (ref "RM1") (pin "4.2") (pinfunction "2_4.2") (pintype "passive"))
      (node (ref "R_PP") (pin "1") (pinfunction "1_1") (pintype "passive"))
      (node (ref "R_RST1") (pin "2") (pinfunction "2_2") (pintype "passive"))
      (node (ref "U1") (pin "6") (pinfunction "VIO_6") (pintype "passive"))
      (node (ref "U3") (pin "108") (pinfunction "VDD_2_108") (pintype "power_in"))
      (node (ref "U3") (pin "121") (pinfunction "VDD_10_121") (pintype "power_in"))
      (node (ref "U3") (pin "131") (pinfunction "VDD_11_131") (pintype "power_in"))
      (node (ref "U3") (pin "144") (pinfunction "VDD_SA_144") (pintype "power_in"))
      (node (ref "U3") (pin "17") (pinfunction "VDD_5_17") (pintype "power_in"))
      (node (ref "U3") (pin "30") (pinfunction "VDD_12_30") (pintype "power_in"))
      (node (ref "U3") (pin "39") (pinfunction "VDD_4_39") (pintype "power_in"))
      (node (ref "U3") (pin "52") (pinfunction "VDD_6_52") (pintype "power_in"))
      (node (ref "U3") (pin "6") (pinfunction "VBAT_6") (pintype "power_in"))
      (node (ref "U3") (pin "62") (pinfunction "VDD_7_62") (pintype "power_in"))
      (node (ref "U3") (pin "72") (pinfunction "VDD_1_72") (pintype "power_in"))
      (node (ref "U3") (pin "84") (pinfunction "VDD_8_84") (pintype "power_in"))
      (node (ref "U3") (pin "95") (pinfunction "VDD_9_95") (pintype "power_in"))
      (node (ref "UEXT1") (pin "1") (pinfunction "1_1") (pintype "passive"))
      (node (ref "UEXT2") (pin "1") (pinfunction "1_1") (pintype "passive"))
      (node (ref "WKUP") (pin "P$1") (pinfunction "0_P$1") (pintype "passive"))
    )
    (net (code "4") (name "/3V3_OUT") (class "Default")
      (node (ref "3V3_ISO") (pin "1") (pinfunction "1_1") (pintype "passive"))
      (node (ref "C3P") (pin "1") (pinfunction "1_1") (pintype "passive"))
      (node (ref "C3V3") (pin "1") (pinfunction "1_1") (pintype "passive"))
      (node (ref "R1_3V3") (pin "2") (pinfunction "2_2") (pintype "passive"))
      (node (ref "U$1") (pin "4") (pinfunction "OUT2_4") (pintype "bidirectional"))
    )
    (net (code "5") (name "/5V") (class "Default")
      (node (ref "5V_ISO") (pin "2") (pinfunction "2_2") (pintype "passive"))
      (node (ref "BBCUR") (pin "1") (pinfunction "1_1") (pintype "passive"))
      (node (ref "C1_BG") (pin "1") (pinfunction "1_1") (pintype "passive"))
      (node (ref "CS1_ADC") (pin "1") (pinfunction "1_1") (pintype "passive"))
      (node (ref "CS2_ADC") (pin "1") (pinfunction "1_1") (pintype "passive"))
      (node (ref "C_AMP") (pin "1") (pinfunction "1_1") (pintype "passive"))
      (node (ref "HCPL092J-00E") (pin "V2") (pinfunction "V2_V2") (pintype "bidirectional"))
      (node (ref "INA148") (pin "V+") (pinfunction "V+_V+") (pintype "bidirectional"))
      (node (ref "LED1") (pin "1") (pinfunction "A1_1") (pintype "passive"))
      (node (ref "R_THERM") (pin "2") (pinfunction "2_2") (pintype "passive"))
      (node (ref "U$13") (pin "1") (pinfunction "1_1") (pintype "bidirectional"))
      (node (ref "U$2") (pin "VIN") (pinfunction "VIN_VIN") (pintype "bidirectional"))
      (node (ref "U$8") (pin "1") (pinfunction "VCC_1") (pintype "power_in"))
      (node (ref "U$8") (pin "7") (pinfunction "~{SHDN}_7") (pintype "input"))
      (node (ref "U$8") (pin "9") (pinfunction "VCC_9") (pintype "power_in"))
    )
    (net (code "6") (name "/5V5") (class "Default")
      (node (ref "5V5_ISO") (pin "2") (pinfunction "2_2") (pintype "passive"))
      (node (ref "CIN") (pin "1") (pinfunction "1_1") (pintype "passive"))
      (node (ref "CS1_CAN") (pin "1") (pinfunction "1_1") (pintype "passive"))
      (node (ref "CS2_CAN") (pin "1") (pinfunction "1_1") (pintype "passive"))
      (node (ref "U$1") (pin "1") (pinfunction "IN_1") (pintype "bidirectional"))
      (node (ref "U$1") (pin "10") (pinfunction "EN1_10") (pintype "bidirectional"))
      (node (ref "U$1") (pin "8") (pinfunction "EN2_8") (pintype "bidirectional"))
      (node (ref "U1") (pin "8") (pinfunction "VCC_8") (pintype "passive"))
    )
    (net (code "7") (name "/5V_OUT") (class "Default")
      (node (ref "5V_ISO") (pin "1") (pinfunction "1_1") (pintype "passive"))
      (node (ref "C1P") (pin "1") (pinfunction "1_1") (pintype "passive"))
      (node (ref "C5V") (pin "1") (pinfunction "1_1") (pintype "passive"))
      (node (ref "R1_5V") (pin "2") (pinfunction "2_2") (pintype "passive"))
      (node (ref "U$1") (pin "3") (pinfunction "OUT1_3") (pintype "bidirectional"))
    )
    (net (code "8") (name "/AREF") (class "Default")
      (node (ref "AREF_EN2") (pin "2") (pinfunction "2_2") (pintype "passive"))
      (node (ref "R_REF") (pin "1") (pinfunction "1_1") (pintype "passive"))
    )
    (net (code "9") (name "/BG_OUT") (class "Default")
      (node (ref "C3_BG") (pin "+") (pinfunction "+_+") (pintype "passive"))
      (node (ref "CB1_ADC") (pin "1") (pinfunction "1_1") (pintype "passive"))
      (node (ref "CB2_ADC") (pin "1") (pinfunction "1_1") (pintype "passive"))
      (node (ref "U$2") (pin "VOUT") (pinfunction "VOUT_VOUT") (pintype "bidirectional"))
      (node (ref "U$8") (pin "8") (pinfunction "VREF_8") (pintype "input"))
    )
    (net (code "10") (name "/BOOT0") (class "Default")
      (node (ref "R_BOOT1") (pin "1") (pinfunction "1_1") (pintype "passive"))
      (node (ref "U3") (pin "138") (pinfunction "BOOT0/VPP_138") (pintype "input"))
    )
    (net (code "11") (name "/C+") (class "Default")
      (node (ref "C1") (pin "1") (pinfunction "1_1") (pintype "passive"))
      (node (ref "CELL") (pin "2") (pinfunction "2_2") (pintype "passive"))
      (node (ref "IC1") (pin "5") (pinfunction "VIN_5") (pintype "input"))
      (node (ref "IC1") (pin "6") (pinfunction "EN_6") (pintype "input"))
      (node (ref "IC1") (pin "7") (pinfunction "PS/SYNC_7") (pintype "input"))
      (node (ref "IC1") (pin "8") (pinfunction "VINA_8") (pintype "input"))
      (node (ref "INA148") (pin "+IN") (pinfunction "+IN_+IN") (pintype "bidirectional"))
      (node (ref "R_BAL") (pin "1") (pinfunction "1_1") (pintype "bidirectional"))
    )
    (net (code "12") (name "/CANH") (class "Default")
      (node (ref "CAN_H_L") (pin "1") (pinfunction "1_1") (pintype "passive"))
      (node (ref "CAN_T") (pin "2") (pinfunction "2_2") (pintype "passive"))
      (node (ref "LEFT_COMM") (pin "1") (pinfunction "1_1") (pintype "passive"))
      (node (ref "RIGHT_COMM") (pin "1") (pinfunction "1_1") (pintype "passive"))
      (node (ref "U1") (pin "17") (pinfunction "CANH_17") (pintype "passive"))
    )
    (net (code "13") (name "/CANL") (class "Default")
      (node (ref "CAN_H_L") (pin "2") (pinfunction "2_2") (pintype "passive"))
      (node (ref "LEFT_COMM") (pin "2") (pinfunction "2_2") (pintype "passive"))
      (node (ref "RIGHT_COMM") (pin "2") (pinfunction "2_2") (pintype "passive"))
      (node (ref "R_CAN") (pin "1") (pinfunction "1_1") (pintype "bidirectional"))
      (node (ref "U1") (pin "15") (pinfunction "CANL_15") (pintype "passive"))
    )
    (net (code "14") (name "/CAN_RX") (class "Default")
      (node (ref "U1") (pin "4") (pinfunction "RXD_4") (pintype "passive"))
      (node (ref "U3") (pin "114") (pinfunction "PD0/FSMC_D2/CAN1_RX_114") (pintype "bidirectional"))
    )
    (net (code "15") (name "/CAN_TX") (class "Default")
      (node (ref "U1") (pin "5") (pinfunction "TXD_5") (pintype "passive"))
      (node (ref "U3") (pin "115") (pinfunction "PD1/FSMC_D3/CAN1_TX_115") (pintype "bidirectional"))
    )
    (net (code "16") (name "/CS") (class "Default")
      (node (ref "ADC_MCU") (pin "6") (pinfunction "6_6") (pintype "passive"))
      (node (ref "HCPL092J-00E") (pin "IN2") (pinfunction "IN2_IN2") (pintype "bidirectional"))
    )
    (net (code "17") (name "/F_IP") (class "Default")
      (node (ref "J_IP") (pin "2") (pinfunction "2_2") (pintype "passive"))
      (node (ref "J_IPF") (pin "2") (pinfunction "2_2") (pintype "passive"))
      (node (ref "U$8") (pin "4") (pinfunction "CH2_4") (pintype "input"))
    )
    (net (code "18") (name "/F_IS") (class "Default")
      (node (ref "J_IS") (pin "2") (pinfunction "2_2") (pintype "passive"))
      (node (ref "J_ISF") (pin "2") (pinfunction "2_2") (pintype "passive"))
      (node (ref "U$8") (pin "5") (pinfunction "CH3_5") (pintype "input"))
    )
    (net (code "19") (name "/F_VOUT") (class "Default")
      (node (ref "J_VF") (pin "2") (pinfunction "2_2") (pintype "passive"))
      (node (ref "J_VOUT") (pin "2") (pinfunction "2_2") (pintype "passive"))
      (node (ref "U$8") (pin "2") (pinfunction "CH0_2") (pintype "input"))
    )
    (net (code "20") (name "/GND") (class "Default")
      (node (ref "ADC_MCU") (pin "11") (pinfunction "11_11") (pintype "passive"))
      (node (ref "ANALOG_I/P") (pin "8") (pinfunction "8_8") (pintype "passive"))
      (node (ref "B0_1/B0_1") (pin "3") (pinfunction "3_3") (pintype "passive"))
      (node (ref "B1_1/B1_1") (pin "3") (pinfunction "3_3") (pintype "passive"))
      (node (ref "BAL_MOS") (pin "S") (pinfunction "S_S") (pintype "bidirectional"))
      (node (ref "BBCUR") (pin "4") (pinfunction "4_4") (pintype "passive"))
      (node (ref "BB_CON") (pin "17") (pinfunction "17_17") (pintype "passive"))
      (node (ref "C1") (pin "2") (pinfunction "2_2") (pintype "passive"))
      (node (ref "C10") (pin "1") (pinfunction "1_1") (pintype "passive"))
      (node (ref "C11") (pin "1") (pinfunction "1_1") (pintype "passive"))
      (node (ref "C12") (pin "1") (pinfunction "1_1") (pintype "passive"))
      (node (ref "C13") (pin "1") (pinfunction "1_1") (pintype "passive"))
      (node (ref "C14") (pin "1") (pinfunction "1_1") (pintype "passive"))
      (node (ref "C15") (pin "1") (pinfunction "1_1") (pintype "passive"))
      (node (ref "C16") (pin "1") (pinfunction "1_1") (pintype "passive"))
      (node (ref "C17") (pin "1") (pinfunction "1_1") (pintype "passive"))
      (node (ref "C18") (pin "1") (pinfunction "1_1") (pintype "passive"))
      (node (ref "C19") (pin "1") (pinfunction "1_1") (pintype "passive"))
      (node (ref "C1_BG") (pin "2") (pinfunction "2_2") (pintype "passive"))
      (node (ref "C2") (pin "2") (pinfunction "2_2") (pintype "passive"))
      (node (ref "C20") (pin "1") (pinfunction "1_1") (pintype "passive"))
      (node (ref "C21") (pin "1") (pinfunction "1_1") (pintype "passive"))
      (node (ref "C22") (pin "1") (pinfunction "1_1") (pintype "passive"))
      (node (ref "C23") (pin "1") (pinfunction "1_1") (pintype "passive"))
      (node (ref "C24") (pin "1") (pinfunction "1_1") (pintype "passive"))
      (node (ref "C25") (pin "2") (pinfunction "2_2") (pintype "passive"))
      (node (ref "C26") (pin "2") (pinfunction "2_2") (pintype "passive"))
      (node (ref "C27") (pin "1") (pinfunction "1_1") (pintype "passive"))
      (node (ref "C28") (pin "1") (pinfunction "1_1") (pintype "passive"))
      (node (ref "C2_BG") (pin "2") (pinfunction "2_2") (pintype "passive"))
      (node (ref "C3") (pin "2") (pinfunction "2_2") (pintype "passive"))
      (node (ref "C3V3") (pin "2") (pinfunction "2_2") (pintype "passive"))
      (node (ref "C3_BG") (pin "-") (pinfunction "-_-") (pintype "passive"))
      (node (ref "C4") (pin "1") (pinfunction "1_1") (pintype "passive"))
      (node (ref "C5") (pin "2") (pinfunction "2_2") (pintype "passive"))
      (node (ref "C5V") (pin "2") (pinfunction "2_2") (pintype "passive"))
      (node (ref "C6") (pin "1") (pinfunction "1_1") (pintype "passive"))
      (node (ref "C7") (pin "2") (pinfunction "2_2") (pintype "passive"))
      (node (ref "C8") (pin "2") (pinfunction "2_2") (pintype "passive"))
      (node (ref "C9") (pin "1") (pinfunction "1_1") (pintype "passive"))
      (node (ref "CB1_ADC") (pin "2") (pinfunction "2_2") (pintype "passive"))
      (node (ref "CB2_ADC") (pin "2") (pinfunction "2_2") (pintype "passive"))
      (node (ref "CELL") (pin "1") (pinfunction "1_1") (pintype "passive"))
      (node (ref "CF") (pin "2") (pinfunction "2_2") (pintype "passive"))
      (node (ref "CIN") (pin "2") (pinfunction "2_2") (pintype "passive"))
      (node (ref "CIN1_CAN") (pin "2") (pinfunction "2_2") (pintype "passive"))
      (node (ref "CIN2_CAN") (pin "2") (pinfunction "2_2") (pintype "passive"))
      (node (ref "CNR") (pin "2") (pinfunction "2_2") (pintype "passive"))
      (node (ref "CP") (pin "2") (pinfunction "2_2") (pintype "passive"))
      (node (ref "CS") (pin "2") (pinfunction "2_2") (pintype "passive"))
      (node (ref "CS1_ADC") (pin "2") (pinfunction "2_2") (pintype "passive"))
      (node (ref "CS1_CAN") (pin "2") (pinfunction "2_2") (pintype "passive"))
      (node (ref "CS2_ADC") (pin "2") (pinfunction "2_2") (pintype "passive"))
      (node (ref "CS2_CAN") (pin "2") (pinfunction "2_2") (pintype "passive"))
      (node (ref "C_AMP") (pin "2") (pinfunction "2_2") (pintype "passive"))
      (node (ref "C_LT/1") (pin "2") (pinfunction "2_2") (pintype "passive"))
      (node (ref "C_RT/1") (pin "2") (pinfunction "2_2") (pintype "passive"))
      (node (ref "DS2401") (pin "GND") (pinfunction "GND_GND") (pintype "bidirectional"))
      (node (ref "HCPL092J-00E") (pin "G2") (pinfunction "G2_G2") (pintype "bidirectional"))
      (node (ref "HCPL092J-00E") (pin "G22") (pinfunction "G22_G22") (pintype "bidirectional"))
      (node (ref "IC1") (pin "3") (pinfunction "PGND_3") (pintype "power_in"))
      (node (ref "IC1") (pin "9") (pinfunction "GND_9") (pintype "power_in"))
      (node (ref "IC1") (pin "TH") (pinfunction "TH_TH") (pintype "bidirectional"))
      (node (ref "INA148") (pin "-IN") (pinfunction "-IN_-IN") (pintype "bidirectional"))
      (node (ref "INA148") (pin "REF") (pinfunction "REF_REF") (pintype "bidirectional"))
      (node (ref "INA148") (pin "V-") (pinfunction "V-_V-") (pintype "bidirectional"))
      (node (ref "JTAG") (pin "10") (pinfunction "10_10") (pintype "passive"))
      (node (ref "JTAG") (pin "12") (pinfunction "12_12") (pintype "passive"))
      (node (ref "JTAG") (pin "14") (pinfunction "14_14") (pintype "passive"))
      (node (ref "JTAG") (pin "16") (pinfunction "16_16") (pintype "passive"))
      (node (ref "JTAG") (pin "18") (pinfunction "18_18") (pintype "passive"))
      (node (ref "JTAG") (pin "20") (pinfunction "20_20") (pintype "passive"))
      (node (ref "JTAG") (pin "4") (pinfunction "4_4") (pintype "passive"))
      (node (ref "JTAG") (pin "6") (pinfunction "6_6") (pintype "passive"))
      (node (ref "JTAG") (pin "8") (pinfunction "8_8") (pintype "passive"))
      (node (ref "J_IP") (pin "3") (pinfunction "3_3") (pintype "passive"))
      (node (ref "J_IS") (pin "3") (pinfunction "3_3") (pintype "passive"))
      (node (ref "J_VOUT") (pin "3") (pinfunction "3_3") (pintype "passive"))
      (node (ref "LCD1") (pin "27") (pinfunction "GND_27") (pintype "power_in"))
      (node (ref "LCD1") (pin "37") (pinfunction "R/~{W}_37") (pintype "input"))
      (node (ref "LEFT_COMM") (pin "5") (pinfunction "5_5") (pintype "passive"))
      (node (ref "LEFT_TX") (pin "4") (pinfunction "4_4") (pintype "passive"))
      (node (ref "PF") (pin "18") (pinfunction "18_18") (pintype "passive"))
      (node (ref "PG") (pin "18") (pinfunction "18_18") (pintype "passive"))
      (node (ref "Q2") (pin "GND") (pinfunction "GND_GND") (pintype "bidirectional"))
      (node (ref "R2_3V3") (pin "1") (pinfunction "1_1") (pintype "passive"))
      (node (ref "R2_5V") (pin "1") (pinfunction "1_1") (pintype "passive"))
      (node (ref "R2_FB") (pin "1") (pinfunction "1_1") (pintype "passive"))
      (node (ref "R9") (pin "2") (pinfunction "2_2") (pintype "passive"))
      (node (ref "RESET") (pin "P$2") (pinfunction "1_P$2") (pintype "passive"))
      (node (ref "RIGHT_COMM") (pin "9") (pinfunction "9_9") (pintype "passive"))
      (node (ref "RIGHT_TX1") (pin "4") (pinfunction "4_4") (pintype "passive"))
      (node (ref "RM1") (pin "2.1") (pinfunction "1_2.1") (pintype "passive"))
      (node (ref "RM3") (pin "1.2") (pinfunction "2_1.2") (pintype "passive"))
      (node (ref "RM3") (pin "2.2") (pinfunction "2_2.2") (pintype "passive"))
      (node (ref "RM3") (pin "3.2") (pinfunction "2_3.2") (pintype "passive"))
      (node (ref "RWK2") (pin "1") (pinfunction "1_1") (pintype "passive"))
      (node (ref "T1") (pin "1") (pinfunction "E_1") (pintype "passive"))
      (node (ref "THERM") (pin "2") (pinfunction "2_2") (pintype "passive"))
      (node (ref "U$1") (pin "5") (pinfunction "GND_5") (pintype "bidirectional"))
      (node (ref "U$1") (pin "TH") (pinfunction "TH_TH") (pintype "bidirectional"))
      (node (ref "U$13") (pin "2") (pinfunction "2_2") (pintype "bidirectional"))
      (node (ref "U$2") (pin "GND") (pinfunction "GND_GND") (pintype "bidirectional"))
      (node (ref "U$3") (pin "K") (pinfunction "C_K") (pintype "passive"))
      (node (ref "U$4") (pin "K") (pinfunction "C_K") (pintype "passive"))
      (node (ref "U$5") (pin "K") (pinfunction "C_K") (pintype "passive"))
      (node (ref "U$8") (pin "10") (pinfunction "GND_10") (pintype "power_in"))
      (node (ref "U$8") (pin "11") (pinfunction "GND_11") (pintype "power_in"))
      (node (ref "U$8") (pin "6") (pinfunction "COM_6") (pintype "input"))
      (node (ref "U1") (pin "1") (pinfunction "GND1_1") (pintype "passive"))
      (node (ref "U1") (pin "10") (pinfunction "GND1_5_10") (pintype "passive"))
      (node (ref "U1") (pin "3") (pinfunction "GND1_2_3") (pintype "passive"))
      (node (ref "U1") (pin "7") (pinfunction "GND1_4_7") (pintype "passive"))
      (node (ref "U1") (pin "9") (pinfunction "GND1_3_9") (pintype "passive"))
      (node (ref "U3") (pin "107") (pinfunction "VSS_2_107") (pintype "power_in"))
      (node (ref "U3") (pin "120") (pinfunction "VSS_10_120") (pintype "power_in"))
      (node (ref "U3") (pin "130") (pinfunction "VSS_11_130") (pintype "power_in"))
      (node (ref "U3") (pin "16") (pinfunction "VSS_5_16") (pintype "power_in"))
      (node (ref "U3") (pin "31") (pinfunction "VSSA_31") (pintype "power_in"))
      (node (ref "U3") (pin "38") (pinfunction "VSS_4_38") (pintype "power_in"))
      (node (ref "U3") (pin "51") (pinfunction "VSS_6_51") (pintype "power_in"))
      (node (ref "U3") (pin "61") (pinfunction "VSS_7_61") (pintype "power_in"))
      (node (ref "U3") (pin "83") (pinfunction "VSS_8_83") (pintype "power_in"))
      (node (ref "U3") (pin "94") (pinfunction "VSS_9_94") (pintype "power_in"))
      (node (ref "UEXT1") (pin "2") (pinfunction "2_2") (pintype "passive"))
      (node (ref "UEXT2") (pin "2") (pinfunction "2_2") (pintype "passive"))
      (node (ref "VOM_1271") (pin "2") (pinfunction "2_2") (pintype "bidirectional"))
      (node (ref "VOM_1271") (pin "3") (pinfunction "3_3") (pintype "bidirectional"))
    )
    (net (code "21") (name "/GND2") (class "Default")
      (node (ref "C_VISO1") (pin "2") (pinfunction "2_2") (pintype "passive"))
      (node (ref "C_VISO2") (pin "2") (pinfunction "2_2") (pintype "passive"))
      (node (ref "C_VISO3") (pin "2") (pinfunction "2_2") (pintype "passive"))
      (node (ref "C_VISO4") (pin "2") (pinfunction "2_2") (pintype "passive"))
      (node (ref "LEFT_COMM") (pin "3") (pinfunction "3_3") (pintype "passive"))
      (node (ref "RIGHT_COMM") (pin "3") (pinfunction "3_3") (pintype "passive"))
      (node (ref "U1") (pin "11") (pinfunction "GND2_2_11") (pintype "passive"))
      (node (ref "U1") (pin "13") (pinfunction "GND2_4_13") (pintype "passive"))
      (node (ref "U1") (pin "16") (pinfunction "GND2_3_16") (pintype "passive"))
      (node (ref "U1") (pin "18") (pinfunction "RS_18") (pintype "passive"))
      (node (ref "U1") (pin "20") (pinfunction "GND2_20") (pintype "passive"))
    )
    (net (code "22") (name "/GND_1") (class "Default")
      (node (ref "C_LT/2") (pin "2") (pinfunction "2_2") (pintype "passive"))
      (node (ref "LEFT_COMM") (pin "9") (pinfunction "9_9") (pintype "passive"))
      (node (ref "LEFT_TX") (pin "7") (pinfunction "7_7") (pintype "passive"))
    )
    (net (code "23") (name "/GND_2") (class "Default")
      (node (ref "C_RT/2") (pin "2") (pinfunction "2_2") (pintype "passive"))
      (node (ref "RIGHT_COMM") (pin "5") (pinfunction "5_5") (pintype "passive"))
      (node (ref "RIGHT_TX1") (pin "7") (pinfunction "7_7") (pintype "passive"))
    )
    (net (code "24") (name "/GSPI") (class "Default")
      (node (ref "ADC_MCU") (pin "12") (pinfunction "12_12") (pintype "passive"))
      (node (ref "HCPL092J-00E") (pin "G1") (pinfunction "G1_G1") (pintype "bidirectional"))
      (node (ref "HCPL092J-00E") (pin "G11") (pinfunction "G11_G11") (pintype "bidirectional"))
      (node (ref "U$14") (pin "2") (pinfunction "2_2") (pintype "bidirectional"))
    )
    (net (code "25") (name "/IP") (class "Default")
      (node (ref "BBCUR") (pin "2") (pinfunction "2_2") (pintype "passive"))
      (node (ref "J_IP") (pin "1") (pinfunction "1_1") (pintype "passive"))
      (node (ref "RP") (pin "1") (pinfunction "1_1") (pintype "passive"))
    )
    (net (code "26") (name "/IPF") (class "Default")
      (node (ref "CP") (pin "1") (pinfunction "1_1") (pintype "passive"))
      (node (ref "J_IPF") (pin "1") (pinfunction "1_1") (pintype "passive"))
      (node (ref "RP") (pin "2") (pinfunction "2_2") (pintype "passive"))
    )
    (net (code "27") (name "/IS") (class "Default")
      (node (ref "BBCUR") (pin "3") (pinfunction "3_3") (pintype "passive"))
      (node (ref "J_IS") (pin "1") (pinfunction "1_1") (pintype "passive"))
      (node (ref "RS") (pin "1") (pinfunction "1_1") (pintype "passive"))
    )
    (net (code "28") (name "/ISF") (class "Default")
      (node (ref "CS") (pin "1") (pinfunction "1_1") (pintype "passive"))
      (node (ref "J_ISF") (pin "1") (pinfunction "1_1") (pintype "passive"))
      (node (ref "RS") (pin "2") (pinfunction "2_2") (pintype "passive"))
    )
    (net (code "29") (name "/MISO") (class "Default")
      (node (ref "ADC_MCU") (pin "10") (pinfunction "10_10") (pintype "passive"))
      (node (ref "HCPL092J-00E") (pin "OUT4") (pinfunction "O4_OUT4") (pintype "bidirectional"))
    )
    (net (code "30") (name "/MOSI") (class "Default")
      (node (ref "ADC_MCU") (pin "8") (pinfunction "8_8") (pintype "passive"))
      (node (ref "HCPL092J-00E") (pin "IN3") (pinfunction "IN3_IN3") (pintype "bidirectional"))
    )
    (net (code "31") (name "/PA0{slash}USART4_TX_LEFT") (class "Default")
      (node (ref "LEFT_TX") (pin "2") (pinfunction "DIN_2") (pintype "passive"))
      (node (ref "U3") (pin "34") (pinfunction "PA0/WKUP/USART2_CTS/USART4_TX/ETH_MII_CRS/TIM2_CH1_ETR/TIM5_CH1/TIM8_ETR/ADC123_CH0_34") (pintype "bidirectional"))
    )
    (net (code "32") (name "/PA0{slash}USART4_TX_LEFT_O{slash}P") (class "Default")
      (node (ref "LEFT_COMM") (pin "7") (pinfunction "7_7") (pintype "passive"))
      (node (ref "LEFT_TX") (pin "6") (pinfunction "DOUT_6") (pintype "passive"))
    )
    (net (code "33") (name "/PA1{slash}USART4_RX_LEFT") (class "Default")
      (node (ref "LEFT_COMM") (pin "6") (pinfunction "6_6") (pintype "passive"))
      (node (ref "U3") (pin "35") (pinfunction "PA1/USART2_RTS/USART4_RX/ETH_RMII_REF_CLK/ETH_MII_RX_CLK/TIM5_CH2/TIM2_CH2/ADC123_IN1_35") (pintype "bidirectional"))
    )
    (net (code "34") (name "/PA2{slash}USART2_TX") (class "Default")
      (node (ref "U3") (pin "36") (pinfunction "PA2/USART2_TX/TIM5_CH3/TIM9_CH1/TIM2_CH3/ETH_MDIO/ADC123_IN2_36") (pintype "bidirectional"))
      (node (ref "UEXT1") (pin "3") (pinfunction "3_3") (pintype "passive"))
    )
    (net (code "35") (name "/PA3{slash}USART2_RX") (class "Default")
      (node (ref "U3") (pin "37") (pinfunction "PA3/USART2_RX/TIM5_CH4/TIM9_CH2/TIM2_CH4/OTG_HS_ULPI_D0/ETH_MII_COL/ADC123_IN3_37") (pintype "bidirectional"))
      (node (ref "UEXT1") (pin "4") (pinfunction "4_4") (pintype "passive"))
    )
    (net (code "36") (name "/PA4{slash}SPI1_NSS") (class "Default")
      (node (ref "ADC_MCU") (pin "5") (pinfunction "5_5") (pintype "passive"))
      (node (ref "U3") (pin "40") (pinfunction "PA4/SPI1_NSS/SPI3_NSS/USART2_CK/DCMI_HSYNC/OTG_HS_SOF/I2S3_WS/ADC12_IN4/DAC1_OUT_40") (pintype "bidirectional"))
    )
    (net (code "37") (name "/PA5{slash}SPI1_SCK") (class "Default")
      (node (ref "ADC_MCU") (pin "3") (pinfunction "3_3") (pintype "passive"))
      (node (ref "U3") (pin "41") (pinfunction "PA5/SPI1_SCK/OTG_HS_ULPI_CK/TIM2_CH1_ETR/TIM8_CHIN/ADC12_IN5/DAC2_OUT_41") (pintype "bidirectional"))
    )
    (net (code "38") (name "/PA6{slash}SPI1_MISO") (class "Default")
      (node (ref "ADC_MCU") (pin "9") (pinfunction "9_9") (pintype "passive"))
      (node (ref "U3") (pin "42") (pinfunction "PA6/SPI1_MISO/TIM8_BKIN/TIM13_CH1/DCMI_PIXCLK/TIM3_CH1/TIM1_BKIN/ADC12_IN6_42") (pintype "bidirectional"))
    )
    (net (code "39") (name "/PA7{slash}SPI1_MOSI") (class "Default")
      (node (ref "ADC_MCU") (pin "7") (pinfunction "7_7") (pintype "passive"))
      (node (ref "U3") (pin "43") (pinfunction "PA7/SPI1_MOSI/TIM8_CH1N/TIM14_CH1/TIM3_CH2/ETH_MII_RX_DV/TIM1_CH1N/RMII_CRS_DV/ADC12_IN7_43") (pintype "bidirectional"))
    )
    (net (code "40") (name "/PA8") (class "Default")
      (node (ref "DS2401") (pin "DATA") (pinfunction "DATA_DATA") (pintype "bidirectional"))
      (node (ref "R_PP") (pin "2") (pinfunction "2_2") (pintype "passive"))
      (node (ref "U3") (pin "100") (pinfunction "PA8/MCO1/USART1_CK/TIM1_CH1/I2C3_SCL/OTG_FS_SOF_100") (pintype "bidirectional"))
    )
    (net (code "41") (name "/PA9{slash}USART1_TX_RIGHT") (class "Default")
      (node (ref "RIGHT_TX1") (pin "2") (pinfunction "DIN_2") (pintype "passive"))
      (node (ref "U3") (pin "101") (pinfunction "PA9/USART1_TX/TIM1_CH2/I2C3_SMBA/DCMI_D0/OTG_FS_VBUS_101") (pintype "bidirectional"))
    )
    (net (code "42") (name "/PA9{slash}USART1_TX_RIGHT_O{slash}P") (class "Default")
      (node (ref "RIGHT_COMM") (pin "6") (pinfunction "6_6") (pintype "passive"))
      (node (ref "RIGHT_TX1") (pin "6") (pinfunction "DOUT_6") (pintype "passive"))
    )
    (net (code "43") (name "/PA10{slash}USART1_RX_RIGHT") (class "Default")
      (node (ref "RIGHT_COMM") (pin "7") (pinfunction "7_7") (pintype "passive"))
      (node (ref "U3") (pin "102") (pinfunction "PA10/USART1_RX/TIM1_CH3/OTG_FS_ID/DCMI_D1_102") (pintype "bidirectional"))
    )
    (net (code "44") (name "/PA11{slash}LED_RED") (class "Default")
      (node (ref "RR") (pin "2") (pinfunction "2_2") (pintype "passive"))
      (node (ref "U3") (pin "103") (pinfunction "PA11/USART1_CTS/CAN1_RX/TIM1_CH4/OTG_FS_DM_103") (pintype "bidirectional"))
    )
    (net (code "45") (name "/PA12") (class "Default")
      (node (ref "U3") (pin "104") (pinfunction "PA12/USART1_RTS/CAN1_TX/TIM1_ETR/OTG_FS_DP_104") (pintype "bidirectional"))
    )
    (net (code "46") (name "/PA13{slash}TMS") (class "Default")
      (node (ref "JTAG") (pin "7") (pinfunction "7_7") (pintype "passive"))
      (node (ref "RM1") (pin "3.1") (pinfunction "1_3.1") (pintype "passive"))
      (node (ref "U3") (pin "105") (pinfunction "PA13/JTMS-SWDIO_105") (pintype "bidirectional"))
    )
    (net (code "47") (name "/PA14{slash}TCK") (class "Default")
      (node (ref "JTAG") (pin "9") (pinfunction "9_9") (pintype "passive"))
      (node (ref "RM1") (pin "2.2") (pinfunction "2_2.2") (pintype "passive"))
      (node (ref "U3") (pin "109") (pinfunction "PA14/JTCK-SWCLK_109") (pintype "bidirectional"))
    )
    (net (code "48") (name "/PA15{slash}TDI") (class "Default")
      (node (ref "JTAG") (pin "5") (pinfunction "5_5") (pintype "passive"))
      (node (ref "RM1") (pin "1.1") (pinfunction "1_1.1") (pintype "passive"))
      (node (ref "U3") (pin "110") (pinfunction "PA15/JTDI/SPI3_NSS/I2S3_WS/TIM2_CH1_ETR/SPI1_NSS_110") (pintype "bidirectional"))
    )
    (net (code "49") (name "/PB0{slash}ADC12_IN8") (class "Default")
      (node (ref "ANALOG_I/P") (pin "5") (pinfunction "5_5") (pintype "passive"))
      (node (ref "U3") (pin "46") (pinfunction "PB0/TIM3_CH3/TIM8_CH2N/OTG_HS_ULPI_D1/ETH_MII_RXD2/TIM1_CH2N/ADC12_IN8_46") (pintype "bidirectional"))
    )
    (net (code "50") (name "/PB1{slash}ADC12_IN9") (class "Default")
      (node (ref "ANALOG_I/P") (pin "6") (pinfunction "6_6") (pintype "passive"))
      (node (ref "U3") (pin "47") (pinfunction "PB1/TIM3_CH4/TIM8_CH3N/OTG_HS_ULPI_D2/ETH_MII_RXD3/OTG_HS_INTN/TIM1_CH3N/ADC12_IN9_47") (pintype "bidirectional"))
    )
    (net (code "51") (name "/PB3{slash}TDO") (class "Default")
      (node (ref "JTAG") (pin "13") (pinfunction "13_13") (pintype "passive"))
      (node (ref "R14") (pin "1") (pinfunction "1_1") (pintype "passive"))
      (node (ref "U3") (pin "133") (pinfunction "PB3/JTDO/TRACESWO/SPI3_SCK/I2S3_CK/TIM2_CH2/SPI1_SCK_133") (pintype "bidirectional"))
    )
    (net (code "52") (name "/PB4{slash}TRST") (class "Default")
      (node (ref "JTAG") (pin "3") (pinfunction "3_3") (pintype "passive"))
      (node (ref "R-T1") (pin "1") (pinfunction "1_1") (pintype "passive"))
      (node (ref "RM1") (pin "4.1") (pinfunction "1_4.1") (pintype "passive"))
      (node (ref "U3") (pin "134") (pinfunction "PB4/NJTRST/SPI3_MISO/TIM3_CH1/SPI1_MISO_134") (pintype "bidirectional"))
    )
    (net (code "53") (name "/PB5{slash}SPI1_MOSI") (class "Default")
      (node (ref "U3") (pin "135") (pinfunction "PB5/I2C1_SMBA/CAN2_RX/OTG_HS_ULPI_D7/ETH_PPS_OUT/TIM3_CH2/SPI1_MOSI/SPI3_MOSI/DCMI_D10/I2S3_SD_135") (pintype "bidirectional"))
    )
    (net (code "54") (name "/PB6{slash}WKUP") (class "Default")
      (node (ref "RWK1") (pin "2") (pinfunction "2_2") (pintype "passive"))
      (node (ref "U3") (pin "136") (pinfunction "PB6/I2C1_SCL/TIM4_CH1/CAN2_TX/OTG_FS_INTN/DCMI_D5/USART1_TX_136") (pintype "bidirectional"))
    )
    (net (code "55") (name "/PB7{slash}LED") (class "Default")
      (node (ref "LED") (pin "C") (pinfunction "C_C") (pintype "passive"))
      (node (ref "U3") (pin "137") (pinfunction "PB7/I2C1_SDA/FSMC_NL/DCMI_VSYNC/USART1_RX/TIM4_CH2_137") (pintype "bidirectional"))
    )
    (net (code "56") (name "/PB8{slash}I2C1_SCL") (class "Default")
      (node (ref "R99") (pin "1") (pinfunction "1_1") (pintype "passive"))
      (node (ref "U3") (pin "139") (pinfunction "PB8/TIM4_CH3/SDIO_D4/TIM10_CH1/DCMI_D6/OTG_FS_SCL/ETH_MII_TXD3/I2C1_SCL/CAN1_RX_139") (pintype "bidirectional"))
      (node (ref "UEXT1") (pin "5") (pinfunction "5_5") (pintype "passive"))
    )
    (net (code "57") (name "/PB9{slash}I2C1_SDA") (class "Default")
      (node (ref "R100") (pin "1") (pinfunction "1_1") (pintype "passive"))
      (node (ref "U3") (pin "140") (pinfunction "PB9/SPI2_NSS/I2S2_WS/TIM4_CH4/TIM11_CH1/OTG_FS_SDA/SDIO_D5/DCMI_D7/I2C1_SDA/CAN1_TX_140") (pintype "bidirectional"))
      (node (ref "UEXT1") (pin "6") (pinfunction "6_6") (pintype "passive"))
    )
    (net (code "58") (name "/PB10{slash}I2C2_SCL") (class "Default")
      (node (ref "R49") (pin "1") (pinfunction "1_1") (pintype "passive"))
      (node (ref "U3") (pin "69") (pinfunction "PB10/SPI2_SCK/I2S2_CK/I2C2_SCL/USART3_TX/OTG_HS_ULPI_D3/ETH_MII_RX_ER/OTG_HS_SCL/TIM2_CH3_69") (pintype "bidirectional"))
      (node (ref "UEXT2") (pin "5") (pinfunction "5_5") (pintype "passive"))
    )
    (net (code "59") (name "/PB11{slash}I2C2_SDA") (class "Default")
      (node (ref "R50") (pin "1") (pinfunction "1_1") (pintype "passive"))
      (node (ref "U3") (pin "70") (pinfunction "PB11/I2C2_SDA/USART3_RX/OTG_HS_ULPI_D4/ETH_RMII_TX_EN/ETH_MII_TX_EN/OTG_HS_SDA/TIM2_CH4_70") (pintype "bidirectional"))
      (node (ref "UEXT2") (pin "6") (pinfunction "6_6") (pintype "passive"))
    )
    (net (code "60") (name "/PB12{slash}SPI2_NSS") (class "Default")
      (node (ref "U3") (pin "73") (pinfunction "PB12/SPI2_NSS/I2S2_WS/I2C2_SMBA/USART3_CK/TIM1_BKIN/CAN2_RX/OTG_HS_ULPI_D5/ETH_RMII_TXD0/ETH_MII_TXD0/OTG_HS_ID_73") (pintype "bidirectional"))
      (node (ref "UEXT2") (pin "10") (pinfunction "10_10") (pintype "passive"))
    )
    (net (code "61") (name "/PB13{slash}SPI2_SCK") (class "Default")
      (node (ref "U3") (pin "74") (pinfunction "PB13/SPI2_SCK/I2S2_CK/USART3_CTS/TIM1_CH1N/CAN2_TX/OTG_HS_ULPI_D6/ETH_RMII_TXD1/ETH_MII_TXD1/OTG_HS_VBUS_74") (pintype "bidirectional"))
      (node (ref "UEXT2") (pin "9") (pinfunction "9_9") (pintype "passive"))
    )
    (net (code "62") (name "/PB14{slash}SPI2_MISO") (class "Default")
      (node (ref "U3") (pin "75") (pinfunction "PB14/SPI2_MISO/TIM1_CH2N/TIM12_CH1/OTG_HS_DM/USART3_RTS/TIM8_CH2N_75") (pintype "bidirectional"))
      (node (ref "UEXT2") (pin "7") (pinfunction "7_7") (pintype "passive"))
    )
    (net (code "63") (name "/PB15{slash}SPI2_MOSI") (class "Default")
      (node (ref "R51") (pin "1") (pinfunction "1_1") (pintype "passive"))
      (node (ref "U3") (pin "76") (pinfunction "PB15/SPI2_MOSI/I2S2_SD/TIM1_CH3N/TIM8_CH3N/TIM12_CH2/OTG_HS_DP_76") (pintype "bidirectional"))
      (node (ref "UEXT2") (pin "8") (pinfunction "8_8") (pintype "passive"))
    )
    (net (code "64") (name "/PC0{slash}ADC123_IN10") (class "Default")
      (node (ref "ANALOG_I/P") (pin "1") (pinfunction "1_1") (pintype "passive"))
      (node (ref "U3") (pin "26") (pinfunction "PC0/OTG_HS_ULPI_STP/ADC123_IN10_26") (pintype "bidirectional"))
    )
    (net (code "65") (name "/PC1{slash}ADC123_IN11") (class "Default")
      (node (ref "ANALOG_I/P") (pin "2") (pinfunction "2_2") (pintype "passive"))
      (node (ref "U3") (pin "27") (pinfunction "PC1/ETH_MDC/ADC123_IN11_27") (pintype "bidirectional"))
    )
    (net (code "66") (name "/PC2") (class "Default")
      (node (ref "U3") (pin "28") (pinfunction "PC2/SPI2_MISO/OTG_HS_ULPI_DIR/ETH_MII_TXD2/ADC123_IN12_28") (pintype "bidirectional"))
    )
    (net (code "67") (name "/PC3") (class "Default")
      (node (ref "C8") (pin "1") (pinfunction "1_1") (pintype "passive"))
      (node (ref "Q2") (pin "2") (pinfunction "2_2") (pintype "passive"))
      (node (ref "R5") (pin "2") (pinfunction "2_2") (pintype "passive"))
      (node (ref "U3") (pin "8") (pinfunction "PC14/OSC32_IN_8") (pintype "bidirectional"))
    )
    (net (code "68") (name "/PC3{slash}SPI2_MOSI") (class "Default")
      (node (ref "U3") (pin "29") (pinfunction "PC3/SPI2_MOSI/I2S2_SD/OTG_HS_ULPI_NXT/ETH_MII_TX_CLK/ADC123_IN13_29") (pintype "bidirectional"))
    )
    (net (code "69") (name "/PC4{slash}ADC12_IN14") (class "Default")
      (node (ref "ANALOG_I/P") (pin "3") (pinfunction "3_3") (pintype "passive"))
      (node (ref "U3") (pin "44") (pinfunction "PC4/ETH_RMII_RX_D0/ETH_MII_RX_D0/ADC12_IN14_44") (pintype "bidirectional"))
    )
    (net (code "70") (name "/PC5{slash}ADC12_IN15") (class "Default")
      (node (ref "ANALOG_I/P") (pin "4") (pinfunction "4_4") (pintype "passive"))
      (node (ref "U3") (pin "45") (pinfunction "PC5/ETH_RMII_RX_D1/ETH_MII_RX_D1/ADC12_IN15_45") (pintype "bidirectional"))
    )
    (net (code "71") (name "/PC6{slash}USART6_TX") (class "Default")
      (node (ref "U3") (pin "96") (pinfunction "PC6/SPI2_MCK/TIM8_CH1/SDIO_D6/USART6_TX/DCMI_D0/TIM3_CH1_96") (pintype "bidirectional"))
      (node (ref "UEXT2") (pin "3") (pinfunction "3_3") (pintype "passive"))
    )
    (net (code "72") (name "/PC7{slash}USART6_RX") (class "Default")
      (node (ref "U3") (pin "97") (pinfunction "PC7/SPI3_MCK/TIM8_CH2/SDIO_D7/USART6_RX/DCMI_D1/TIM3_CH2_97") (pintype "bidirectional"))
      (node (ref "UEXT2") (pin "4") (pinfunction "4_4") (pintype "passive"))
    )
    (net (code "73") (name "/PC8{slash}PAS_BAL") (class "Default")
      (node (ref "R_BALIN") (pin "1") (pinfunction "1_1") (pintype "passive"))
      (node (ref "U3") (pin "98") (pinfunction "PC8/TIM8_CH3/SDIO_D0/TIM3_CH3/USART6_CK/DCMI_D2_98") (pintype "bidirectional"))
    )
    (net (code "74") (name "/PC9{slash}SPI3_NSS") (class "Default")
      (node (ref "U3") (pin "99") (pinfunction "PC9/I2S2_CKIN/I2S3_CKIN/MCO2/TIM8_CH4/SDIO_D1/I2C3_SDA/DCMI_D3/TIM3_CH4_99") (pintype "bidirectional"))
      (node (ref "UEXT1") (pin "10") (pinfunction "10_10") (pintype "passive"))
    )
    (net (code "75") (name "/PC10{slash}SPI3_SCK") (class "Default")
      (node (ref "U3") (pin "111") (pinfunction "PC10/SPI3_SCK/I2S3_CK/UART4_TX/SDIO_D2/DCMI_D8/USART3_TX_111") (pintype "bidirectional"))
      (node (ref "UEXT1") (pin "9") (pinfunction "9_9") (pintype "passive"))
    )
    (net (code "76") (name "/PC11{slash}SPI3_MISO") (class "Default")
      (node (ref "U3") (pin "112") (pinfunction "PC11/UART4_RX/SPI3_MISO/SDIO_D3/DCMI_D4/USART3_RX_112") (pintype "bidirectional"))
      (node (ref "UEXT1") (pin "7") (pinfunction "7_7") (pintype "passive"))
    )
    (net (code "77") (name "/PC12{slash}SPI3_MOSI") (class "Default")
      (node (ref "R101") (pin "1") (pinfunction "1_1") (pintype "passive"))
      (node (ref "U3") (pin "113") (pinfunction "PC12/UART5_TX/SDIO_CK/DCMI_D9/SPI3_MOSI/I2S3_SD/USART3_CK_113") (pintype "bidirectional"))
      (node (ref "UEXT1") (pin "8") (pinfunction "8_8") (pintype "passive"))
    )
    (net (code "78") (name "/PC13") (class "Default")
      (node (ref "U3") (pin "7") (pinfunction "PC13/RTC_AF1_7") (pintype "bidirectional"))
    )
    (net (code "79") (name "/PD2{slash}D0_LCD") (class "Default")
      (node (ref "LCD1") (pin "35") (pinfunction "D0_35") (pintype "bidirectional"))
      (node (ref "U3") (pin "116") (pinfunction "PD2/TIM3_ETR/UART5_RX/SDIO_CMD/DCMI_D11_116") (pintype "bidirectional"))
    )
    (net (code "80") (name "/PD3{slash}D1_LCD") (class "Default")
      (node (ref "LCD1") (pin "34") (pinfunction "D1_34") (pintype "bidirectional"))
      (node (ref "U3") (pin "117") (pinfunction "PD3/FSMC_CLK/USART2_CTS_117") (pintype "bidirectional"))
    )
    (net (code "81") (name "/PD4{slash}D2_LCD") (class "Default")
      (node (ref "LCD1") (pin "33") (pinfunction "D2_33") (pintype "bidirectional"))
      (node (ref "U3") (pin "118") (pinfunction "PD4/FSMC_NOE/USART2_RTS_118") (pintype "bidirectional"))
    )
    (net (code "82") (name "/PD5{slash}D3_LCD") (class "Default")
      (node (ref "LCD1") (pin "32") (pinfunction "D3_32") (pintype "bidirectional"))
      (node (ref "U3") (pin "119") (pinfunction "PD5/FSMC_NWE/USART2_TX_119") (pintype "bidirectional"))
    )
    (net (code "83") (name "/PD6{slash}D4_LCD") (class "Default")
      (node (ref "LCD1") (pin "31") (pinfunction "D4_31") (pintype "bidirectional"))
      (node (ref "U3") (pin "122") (pinfunction "PD6/FSMC_NWAIT/USART2_RX_122") (pintype "bidirectional"))
    )
    (net (code "84") (name "/PD7{slash}D5_LCD") (class "Default")
      (node (ref "LCD1") (pin "30") (pinfunction "D5_30") (pintype "bidirectional"))
      (node (ref "U3") (pin "123") (pinfunction "PD7/USART2_CK/FSMC_NE1/FSMC_NCE2_123") (pintype "bidirectional"))
    )
    (net (code "85") (name "/PD8{slash}D6_LCD") (class "Default")
      (node (ref "LCD1") (pin "29") (pinfunction "D6_29") (pintype "bidirectional"))
      (node (ref "U3") (pin "77") (pinfunction "PD8/FSMC_D13/USART3_TX_77") (pintype "bidirectional"))
    )
    (net (code "86") (name "/PD9") (class "Default")
      (node (ref "BB_CON") (pin "2") (pinfunction "2_2") (pintype "passive"))
      (node (ref "U3") (pin "78") (pinfunction "PD9/FSMC_D14/USART3_RX_78") (pintype "bidirectional"))
    )
    (net (code "87") (name "/PD10") (class "Default")
      (node (ref "BB_CON") (pin "4") (pinfunction "4_4") (pintype "passive"))
      (node (ref "U3") (pin "79") (pinfunction "PD10/FSMC_D15/USART3_CK_79") (pintype "bidirectional"))
    )
    (net (code "88") (name "/PD11") (class "Default")
      (node (ref "BB_CON") (pin "5") (pinfunction "5_5") (pintype "passive"))
      (node (ref "U3") (pin "80") (pinfunction "PD11/FSMC_A16/USART3_CTS_80") (pintype "bidirectional"))
    )
    (net (code "89") (name "/PD12") (class "Default")
      (node (ref "BB_CON") (pin "3") (pinfunction "3_3") (pintype "passive"))
      (node (ref "U3") (pin "81") (pinfunction "PD12/FSMC_A17/TIM4_CH1/USART3_RTS_81") (pintype "bidirectional"))
    )
    (net (code "90") (name "/PD13") (class "Default")
      (node (ref "BB_CON") (pin "6") (pinfunction "6_6") (pintype "passive"))
      (node (ref "U3") (pin "82") (pinfunction "PD13/FSMC_A18/TIM4_CH2_82") (pintype "bidirectional"))
    )
    (net (code "91") (name "/PD14") (class "Default")
      (node (ref "BB_CON") (pin "7") (pinfunction "7_7") (pintype "passive"))
      (node (ref "U3") (pin "85") (pinfunction "PD14/FSMC_D0/TIM4_CH3_85") (pintype "bidirectional"))
    )
    (net (code "92") (name "/PD15{slash}D7_LCD") (class "Default")
      (node (ref "LCD1") (pin "28") (pinfunction "D7_28") (pintype "bidirectional"))
      (node (ref "U3") (pin "86") (pinfunction "PD15/FSMC_D1/TIM4_CH4_86") (pintype "bidirectional"))
    )
    (net (code "93") (name "/PE0{slash}PSB_LCD") (class "Default")
      (node (ref "LCD1") (pin "23") (pinfunction "PSB_23") (pintype "input"))
      (node (ref "U3") (pin "141") (pinfunction "PE0/TIM4_ETR/FSMC_NBL0/DCMI_D2_141") (pintype "bidirectional"))
    )
    (net (code "94") (name "/PE1{slash}RESET_LCD") (class "Default")
      (node (ref "LCD1") (pin "40") (pinfunction "~{RESET}_40") (pintype "input"))
      (node (ref "U3") (pin "142") (pinfunction "PE1/FSMC_NBL1/DCMI_D3_142") (pintype "bidirectional"))
    )
    (net (code "95") (name "/PE2{slash}RS_LCD") (class "Default")
      (node (ref "LCD1") (pin "39") (pinfunction "RS_39") (pintype "input"))
      (node (ref "U3") (pin "1") (pinfunction "PE2/TRACECK/FSMC_A23/ETH_MII_TXD3_1") (pintype "bidirectional"))
    )
    (net (code "96") (name "/PE3") (class "Default")
      (node (ref "BB_CON") (pin "8") (pinfunction "8_8") (pintype "passive"))
      (node (ref "U3") (pin "2") (pinfunction "PE3/TRACED0/FSMC_A19_2") (pintype "bidirectional"))
    )
    (net (code "97") (name "/PE4") (class "Default")
      (node (ref "BB_CON") (pin "9") (pinfunction "9_9") (pintype "passive"))
      (node (ref "U3") (pin "3") (pinfunction "PE4/TRACED1/FSMC_A20/DCMI_D4_3") (pintype "bidirectional"))
    )
    (net (code "98") (name "/PE5") (class "Default")
      (node (ref "BB_CON") (pin "10") (pinfunction "10_10") (pintype "passive"))
      (node (ref "U3") (pin "4") (pinfunction "PE5/TRACED2/FSMC_A21/TIM9_CH1/DCMI_D6_4") (pintype "bidirectional"))
    )
    (net (code "99") (name "/PE6") (class "Default")
      (node (ref "BB_CON") (pin "11") (pinfunction "11_11") (pintype "passive"))
      (node (ref "U3") (pin "5") (pinfunction "PE6/TRACED3/FSMC_A22/TIM9_CH2/DCMI_D7_5") (pintype "bidirectional"))
    )
    (net (code "100") (name "/PE7") (class "Default")
      (node (ref "BB_CON") (pin "12") (pinfunction "12_12") (pintype "passive"))
      (node (ref "U3") (pin "58") (pinfunction "PE7/FSMC_D4/TIM1_ETR_58") (pintype "bidirectional"))
    )
    (net (code "101") (name "/PE8") (class "Default")
      (node (ref "BB_CON") (pin "13") (pinfunction "13_13") (pintype "passive"))
      (node (ref "U3") (pin "59") (pinfunction "PE8/FSMC_D5/TIM1_CH1N_59") (pintype "bidirectional"))
    )
    (net (code "102") (name "/PE9") (class "Default")
      (node (ref "BB_CON") (pin "14") (pinfunction "14_14") (pintype "passive"))
      (node (ref "U3") (pin "60") (pinfunction "PE9/FSMC_D6/TIM1_CH1_60") (pintype "bidirectional"))
    )
    (net (code "103") (name "/PE10") (class "Default")
      (node (ref "BB_CON") (pin "15") (pinfunction "15_15") (pintype "passive"))
      (node (ref "U3") (pin "63") (pinfunction "PE10/FSMC_D7/TIM1_CH2N_63") (pintype "bidirectional"))
    )
    (net (code "104") (name "/PE11") (class "Default")
      (node (ref "BB_CON") (pin "16") (pinfunction "16_16") (pintype "passive"))
      (node (ref "U3") (pin "64") (pinfunction "PE11/FSMC_D8/TIM1_CH2_64") (pintype "bidirectional"))
    )
    (net (code "105") (name "/PE12{slash}CS_LCD") (class "Default")
      (node (ref "LCD1") (pin "38") (pinfunction "~{CSB}_38") (pintype "input"))
      (node (ref "U3") (pin "65") (pinfunction "PE12/FSMC_D9/TIM1_CH3N_65") (pintype "bidirectional"))
    )
    (net (code "106") (name "/PE14{slash}LED_YELLOW") (class "Default")
      (node (ref "RY") (pin "2") (pinfunction "2_2") (pintype "passive"))
      (node (ref "U3") (pin "67") (pinfunction "PE14/FSMC_D11/TIM1_CH4_67") (pintype "bidirectional"))
    )
    (net (code "107") (name "/PE15{slash}LED_ORANGE") (class "Default")
      (node (ref "RO") (pin "2") (pinfunction "2_2") (pintype "passive"))
      (node (ref "U3") (pin "68") (pinfunction "PE15/FSMC_D12/TIM1_BKIN_68") (pintype "bidirectional"))
    )
    (net (code "108") (name "/PF0") (class "Default")
      (node (ref "PF") (pin "2") (pinfunction "2_2") (pintype "passive"))
      (node (ref "U3") (pin "10") (pinfunction "PF0/FSMC_A0/I2C2_SDA_10") (pintype "bidirectional"))
    )
    (net (code "109") (name "/PF1") (class "Default")
      (node (ref "PF") (pin "3") (pinfunction "3_3") (pintype "passive"))
      (node (ref "U3") (pin "11") (pinfunction "PF1/FSMC_A1/I2C2_SCL_11") (pintype "bidirectional"))
    )
    (net (code "110") (name "/PF2") (class "Default")
      (node (ref "PF") (pin "4") (pinfunction "4_4") (pintype "passive"))
      (node (ref "U3") (pin "12") (pinfunction "PF2/FSMC_A2/I2C2_SMBA_12") (pintype "bidirectional"))
    )
    (net (code "111") (name "/PF3") (class "Default")
      (node (ref "PF") (pin "5") (pinfunction "5_5") (pintype "passive"))
      (node (ref "U3") (pin "13") (pinfunction "PF3/FSMC_A3/ADC3_IN9_13") (pintype "bidirectional"))
    )
    (net (code "112") (name "/PF4") (class "Default")
      (node (ref "PF") (pin "6") (pinfunction "6_6") (pintype "passive"))
      (node (ref "U3") (pin "14") (pinfunction "PF4/FSMC_A4/ADC3_IN14_14") (pintype "bidirectional"))
    )
    (net (code "113") (name "/PF5") (class "Default")
      (node (ref "PF") (pin "7") (pinfunction "7_7") (pintype "passive"))
      (node (ref "U3") (pin "15") (pinfunction "PF5/FSMC_A5/ADC3_IN15_15") (pintype "bidirectional"))
    )
    (net (code "114") (name "/PF6") (class "Default")
      (node (ref "PF") (pin "8") (pinfunction "8_8") (pintype "passive"))
      (node (ref "U3") (pin "18") (pinfunction "PF6/TIM10_CH1/FSMC_NIORD/ADC3_IN4_18") (pintype "bidirectional"))
    )
    (net (code "115") (name "/PF7") (class "Default")
      (node (ref "PF") (pin "9") (pinfunction "9_9") (pintype "passive"))
      (node (ref "U3") (pin "19") (pinfunction "PF7/TIM11_CH1/FSMC_NREG/ADC3_IN5_19") (pintype "bidirectional"))
    )
    (net (code "116") (name "/PF8") (class "Default")
      (node (ref "PF") (pin "10") (pinfunction "10_10") (pintype "passive"))
      (node (ref "U3") (pin "20") (pinfunction "PF8/TIM13_CH1/FSMC_NIOWR/ADC3_IN6_20") (pintype "bidirectional"))
    )
    (net (code "117") (name "/PF9") (class "Default")
      (node (ref "PF") (pin "11") (pinfunction "11_11") (pintype "passive"))
      (node (ref "U3") (pin "21") (pinfunction "PF9/TIM14_CH1/FSMC_CD/ADC3_IN7_21") (pintype "bidirectional"))
    )
    (net (code "118") (name "/PF10") (class "Default")
      (node (ref "PF") (pin "12") (pinfunction "12_12") (pintype "passive"))
      (node (ref "U3") (pin "22") (pinfunction "PF10/FSMC_INTR/ADC3_IN8_22") (pintype "bidirectional"))
    )
    (net (code "119") (name "/PF11") (class "Default")
      (node (ref "PF") (pin "13") (pinfunction "13_13") (pintype "passive"))
      (node (ref "U3") (pin "49") (pinfunction "PF11/DCMI_12_49") (pintype "bidirectional"))
    )
    (net (code "120") (name "/PF12") (class "Default")
      (node (ref "PF") (pin "14") (pinfunction "14_14") (pintype "passive"))
      (node (ref "U3") (pin "50") (pinfunction "PF12/FSMC_A6_50") (pintype "bidirectional"))
    )
    (net (code "121") (name "/PF13") (class "Default")
      (node (ref "PF") (pin "15") (pinfunction "15_15") (pintype "passive"))
      (node (ref "U3") (pin "53") (pinfunction "PF13/FSMC_A7_53") (pintype "bidirectional"))
    )
    (net (code "122") (name "/PF14") (class "Default")
      (node (ref "PF") (pin "16") (pinfunction "16_16") (pintype "passive"))
      (node (ref "U3") (pin "54") (pinfunction "PF14/FSMC_A8_54") (pintype "bidirectional"))
    )
    (net (code "123") (name "/PF15") (class "Default")
      (node (ref "PF") (pin "17") (pinfunction "17_17") (pintype "passive"))
      (node (ref "U3") (pin "55") (pinfunction "PF15/FSMC_A9_55") (pintype "bidirectional"))
    )
    (net (code "124") (name "/PG0") (class "Default")
      (node (ref "PG") (pin "2") (pinfunction "2_2") (pintype "passive"))
      (node (ref "U3") (pin "56") (pinfunction "PG0/FSMC_A10_56") (pintype "bidirectional"))
    )
    (net (code "125") (name "/PG1") (class "Default")
      (node (ref "PG") (pin "3") (pinfunction "3_3") (pintype "passive"))
      (node (ref "U3") (pin "57") (pinfunction "PG1/FSMC_A11_57") (pintype "bidirectional"))
    )
    (net (code "126") (name "/PG2") (class "Default")
      (node (ref "PG") (pin "4") (pinfunction "4_4") (pintype "passive"))
      (node (ref "U3") (pin "87") (pinfunction "PG2/FSMC_A12_87") (pintype "bidirectional"))
    )
    (net (code "127") (name "/PG3") (class "Default")
      (node (ref "PG") (pin "5") (pinfunction "5_5") (pintype "passive"))
      (node (ref "U3") (pin "88") (pinfunction "PG3/FSMC_A13_88") (pintype "bidirectional"))
    )
    (net (code "128") (name "/PG4") (class "Default")
      (node (ref "PG") (pin "6") (pinfunction "6_6") (pintype "passive"))
      (node (ref "U3") (pin "89") (pinfunction "PG4/FSMC_A14_89") (pintype "bidirectional"))
    )
    (net (code "129") (name "/PG5") (class "Default")
      (node (ref "PG") (pin "7") (pinfunction "7_7") (pintype "passive"))
      (node (ref "U3") (pin "90") (pinfunction "PG5/FSMC_A15_90") (pintype "bidirectional"))
    )
    (net (code "130") (name "/PG6") (class "Default")
      (node (ref "PG") (pin "8") (pinfunction "8_8") (pintype "passive"))
      (node (ref "U3") (pin "91") (pinfunction "PG6/FSMC_INT2_91") (pintype "bidirectional"))
    )
    (net (code "131") (name "/PG7") (class "Default")
      (node (ref "PG") (pin "9") (pinfunction "9_9") (pintype "passive"))
      (node (ref "U3") (pin "92") (pinfunction "PG7/FSMC_INT3/USART6_CK_92") (pintype "bidirectional"))
    )
    (net (code "132") (name "/PG8") (class "Default")
      (node (ref "PG") (pin "10") (pinfunction "10_10") (pintype "passive"))
      (node (ref "U3") (pin "93") (pinfunction "PG8/USART6_RTS/ETH_PPS_OUT_93") (pintype "bidirectional"))
    )
    (net (code "133") (name "/PG9{slash}LCD_TRAN") (class "Default")
      (node (ref "R_TRAN") (pin "2") (pinfunction "2_2") (pintype "passive"))
      (node (ref "U3") (pin "124") (pinfunction "PG9/USART6_RX/FSMC_NE2/FSMC_NCE3_124") (pintype "bidirectional"))
    )
    (net (code "134") (name "/PG10") (class "Default")
      (node (ref "PG") (pin "12") (pinfunction "12_12") (pintype "passive"))
      (node (ref "U3") (pin "125") (pinfunction "PG10/FSMC_NCE4_1/FSMC_NE3_125") (pintype "bidirectional"))
    )
    (net (code "135") (name "/PG11") (class "Default")
      (node (ref "PG") (pin "13") (pinfunction "13_13") (pintype "passive"))
      (node (ref "U3") (pin "126") (pinfunction "PG11/FSMC_NCE4_2/ETH_MII_TX_EN_126") (pintype "bidirectional"))
    )
    (net (code "136") (name "/PG12") (class "Default")
      (node (ref "PG") (pin "14") (pinfunction "14_14") (pintype "passive"))
      (node (ref "U3") (pin "127") (pinfunction "PG12/FSMC_NE4/USART6_RTS_127") (pintype "bidirectional"))
    )
    (net (code "137") (name "/PG13") (class "Default")
      (node (ref "PG") (pin "15") (pinfunction "15_15") (pintype "passive"))
      (node (ref "U3") (pin "128") (pinfunction "PG13/FSMC_A24/USART6_CTS/ETH_MII_TXD0/ETH_RMII_TXD0_128") (pintype "bidirectional"))
    )
    (net (code "138") (name "/PG14") (class "Default")
      (node (ref "PG") (pin "16") (pinfunction "16_16") (pintype "passive"))
      (node (ref "U3") (pin "129") (pinfunction "PG14/FSMC_A25/USART6_TX/ETH_MII_TXD1/ETH_RMII_TXD1_129") (pintype "bidirectional"))
    )
    (net (code "139") (name "/PG15") (class "Default")
      (node (ref "PG") (pin "17") (pinfunction "17_17") (pintype "passive"))
      (node (ref "U3") (pin "132") (pinfunction "PG15/USART6_CTS/DCMI_D13_132") (pintype "bidirectional"))
    )
    (net (code "140") (name "/RST") (class "Default")
      (node (ref "JTAG") (pin "15") (pinfunction "15_15") (pintype "passive"))
      (node (ref "R-T1") (pin "2") (pinfunction "2_2") (pintype "passive"))
      (node (ref "R_RST2") (pin "1") (pinfunction "1_1") (pintype "passive"))
      (node (ref "U3") (pin "25") (pinfunction "NRST_25") (pintype "power_in"))
    )
    (net (code "141") (name "/SCLK") (class "Default")
      (node (ref "ADC_MCU") (pin "4") (pinfunction "4_4") (pintype "passive"))
      (node (ref "HCPL092J-00E") (pin "IN1") (pinfunction "IN1_IN1") (pintype "bidirectional"))
    )
    (net (code "142") (name "/THERM") (class "Default")
      (node (ref "R_THERM") (pin "1") (pinfunction "1_1") (pintype "passive"))
      (node (ref "THERM") (pin "1") (pinfunction "1_1") (pintype "passive"))
      (node (ref "U$8") (pin "3") (pinfunction "CH1_3") (pintype "input"))
    )
    (net (code "143") (name "/TPS6300_OUT") (class "Default")
      (node (ref "5V5_ISO") (pin "1") (pinfunction "1_1") (pintype "passive"))
      (node (ref "C2") (pin "1") (pinfunction "1_1") (pintype "passive"))
      (node (ref "C3") (pin "1") (pinfunction "1_1") (pintype "passive"))
      (node (ref "IC1") (pin "1") (pinfunction "VOUT_1") (pintype "output"))
      (node (ref "R1_FB") (pin "2") (pinfunction "2_2") (pintype "passive"))
    )
    (net (code "144") (name "/VDD_1") (class "Default")
      (node (ref "C_LT/2") (pin "1") (pinfunction "1_1") (pintype "passive"))
      (node (ref "LEFT_COMM") (pin "8") (pinfunction "8_8") (pintype "passive"))
      (node (ref "LEFT_TX") (pin "8") (pinfunction "8_8") (pintype "passive"))
    )
    (net (code "145") (name "/VDD_2") (class "Default")
      (node (ref "C_RT/2") (pin "1") (pinfunction "1_1") (pintype "passive"))
      (node (ref "RIGHT_COMM") (pin "4") (pinfunction "4_4") (pintype "passive"))
      (node (ref "RIGHT_TX1") (pin "8") (pinfunction "8_8") (pintype "passive"))
    )
    (net (code "146") (name "/VISO") (class "Default")
      (node (ref "C_VISO1") (pin "1") (pinfunction "1_1") (pintype "passive"))
      (node (ref "C_VISO2") (pin "1") (pinfunction "1_1") (pintype "passive"))
      (node (ref "C_VISO3") (pin "1") (pinfunction "1_1") (pintype "passive"))
      (node (ref "C_VISO4") (pin "1") (pinfunction "1_1") (pintype "passive"))
      (node (ref "U1") (pin "12") (pinfunction "VISOOUT_12") (pintype "passive"))
      (node (ref "U1") (pin "19") (pinfunction "VISOIN_19") (pintype "passive"))
    )
    (net (code "147") (name "/VOUT") (class "Default")
      (node (ref "CF") (pin "1") (pinfunction "1_1") (pintype "passive"))
      (node (ref "J_VF") (pin "1") (pinfunction "1_1") (pintype "passive"))
      (node (ref "RF") (pin "2") (pinfunction "2_2") (pintype "passive"))
    )
    (net (code "148") (name "/VOUT_AMP") (class "Default")
      (node (ref "INA148") (pin "VOUT") (pinfunction "VOUT_VOUT") (pintype "bidirectional"))
      (node (ref "J_VCELL") (pin "1") (pinfunction "1_1") (pintype "passive"))
    )
    (net (code "149") (name "/VOUT_BB") (class "Default")
      (node (ref "J_VCELL") (pin "3") (pinfunction "3_3") (pintype "passive"))
    )
    (net (code "150") (name "/VOUT_SEL") (class "Default")
      (node (ref "J_VCELL") (pin "2") (pinfunction "2_2") (pintype "passive"))
      (node (ref "J_VOUT") (pin "1") (pinfunction "1_1") (pintype "passive"))
      (node (ref "RF") (pin "1") (pinfunction "1_1") (pintype "passive"))
    )
    (net (code "151") (name "/VSPI") (class "Default")
      (node (ref "ADC_MCU") (pin "2") (pinfunction "2_2") (pintype "passive"))
      (node (ref "HCPL092J-00E") (pin "V1") (pinfunction "V1_V1") (pintype "bidirectional"))
      (node (ref "U$14") (pin "1") (pinfunction "1_1") (pintype "bidirectional"))
    )
    (net (code "152") (name "Net-(B0_1/B0_1-Pad2)") (class "Default")
      (node (ref "B0_1/B0_1") (pin "2") (pinfunction "2_2") (pintype "passive"))
      (node (ref "R_BOOT1") (pin "2") (pinfunction "2_2") (pintype "passive"))
    )
    (net (code "153") (name "Net-(B1_1/B1_1-Pad2)") (class "Default")
      (node (ref "B1_1/B1_1") (pin "2") (pinfunction "2_2") (pintype "passive"))
      (node (ref "RBOOT2") (pin "2") (pinfunction "2_2") (pintype "passive"))
    )
    (net (code "154") (name "Net-(BAL_MOS-PadD)") (class "Default")
      (node (ref "BAL_MOS") (pin "D") (pinfunction "D_D") (pintype "bidirectional"))
      (node (ref "R_BAL") (pin "2") (pinfunction "2_2") (pintype "bidirectional"))
    )
    (net (code "155") (name "Net-(BAL_MOS-PadG)") (class "Default")
      (node (ref "BAL_MOS") (pin "G") (pinfunction "G_G") (pintype "bidirectional"))
      (node (ref "VOM_1271") (pin "4") (pinfunction "4_4") (pintype "bidirectional"))
    )
    (net (code "156") (name "Net-(C2_BG-Pad1)") (class "Default")
      (node (ref "C2_BG") (pin "1") (pinfunction "1_1") (pintype "passive"))
      (node (ref "U$2") (pin "TRIM/NR") (pinfunction "TRIM/NR_TRIM/NR") (pintype "bidirectional"))
    )
    (net (code "157") (name "Net-(C26-Pad1)") (class "Default")
      (node (ref "C26") (pin "1") (pinfunction "1_1") (pintype "passive"))
      (node (ref "Q1") (pin "2") (pinfunction "2_2") (pintype "passive"))
      (node (ref "R_OSC") (pin "1") (pinfunction "1_1") (pintype "passive"))
    )
    (net (code "158") (name "Net-(CAN_T-Pad1)") (class "Default")
      (node (ref "CAN_T") (pin "1") (pinfunction "1_1") (pintype "passive"))
      (node (ref "R_CAN") (pin "2") (pinfunction "2_2") (pintype "bidirectional"))
    )
    (net (code "159") (name "Net-(HCPL092J-00E-O1)") (class "Default")
      (node (ref "HCPL092J-00E") (pin "OUT1") (pinfunction "O1_OUT1") (pintype "bidirectional"))
      (node (ref "U$8") (pin "16") (pinfunction "DCLK_16") (pintype "input"))
    )
    (net (code "160") (name "Net-(HCPL092J-00E-O2)") (class "Default")
      (node (ref "HCPL092J-00E") (pin "OUT2") (pinfunction "O2_OUT2") (pintype "bidirectional"))
      (node (ref "U$8") (pin "15") (pinfunction "~{CS}_15") (pintype "input"))
    )
    (net (code "161") (name "Net-(HCPL092J-00E-O3)") (class "Default")
      (node (ref "HCPL092J-00E") (pin "OUT3") (pinfunction "O3_OUT3") (pintype "bidirectional"))
      (node (ref "U$8") (pin "14") (pinfunction "DIN_14") (pintype "input"))
    )
    (net (code "162") (name "Net-(IC1-FB)") (class "Default")
      (node (ref "IC1") (pin "10") (pinfunction "FB_10") (pintype "input"))
      (node (ref "R1_FB") (pin "1") (pinfunction "1_1") (pintype "passive"))
      (node (ref "R2_FB") (pin "2") (pinfunction "2_2") (pintype "passive"))
    )
    (net (code "163") (name "Net-(IC1-L1)") (class "Default")
      (node (ref "IC1") (pin "4") (pinfunction "L1_4") (pintype "passive"))
      (node (ref "L1") (pin "L1") (pinfunction "L1_L1") (pintype "bidirectional"))
    )
    (net (code "164") (name "Net-(IC1-L2)") (class "Default")
      (node (ref "IC1") (pin "2") (pinfunction "L2_2") (pintype "passive"))
      (node (ref "L1") (pin "L2") (pinfunction "L2_L2") (pintype "bidirectional"))
    )
    (net (code "165") (name "Net-(LCD1-CAP1N)") (class "Default")
      (node (ref "C_DISP1") (pin "1") (pinfunction "1_1") (pintype "passive"))
      (node (ref "LCD1") (pin "21") (pinfunction "CAP1N_21") (pintype "passive"))
    )
    (net (code "166") (name "Net-(LCD1-CAP1P)") (class "Default")
      (node (ref "C_DISP1") (pin "2") (pinfunction "2_2") (pintype "passive"))
      (node (ref "LCD1") (pin "22") (pinfunction "CAP1P_22") (pintype "passive"))
    )
    (net (code "167") (name "Net-(LCD1-VOUT)") (class "Default")
      (node (ref "C_DISP2") (pin "2") (pinfunction "2_2") (pintype "passive"))
      (node (ref "LCD1") (pin "24") (pinfunction "VOUT_24") (pintype "passive"))
    )
    (net (code "168") (name "Net-(LED-PadA)") (class "Default")
      (node (ref "LED") (pin "A") (pinfunction "A_A") (pintype "passive"))
      (node (ref "RGL") (pin "1") (pinfunction "1_1") (pintype "passive"))
    )
    (net (code "169") (name "Net-(LED1-A2)") (class "Default")
      (node (ref "LED1") (pin "2") (pinfunction "C1_2") (pintype "passive"))
      (node (ref "LED1") (pin "20") (pinfunction "A2_20") (pintype "passive"))
    )
    (net (code "170") (name "Net-(LED1-C2)") (class "Default")
      (node (ref "LED1") (pin "19") (pinfunction "C2_19") (pintype "passive"))
      (node (ref "R_DISP") (pin "2") (pinfunction "2_2") (pintype "passive"))
    )
    (net (code "171") (name "Net-(R10-1.1)") (class "Default")
      (node (ref "C18") (pin "2") (pinfunction "2_2") (pintype "passive"))
      (node (ref "R10") (pin "1") (pinfunction "1.1_1") (pintype "passive"))
      (node (ref "R9") (pin "1") (pinfunction "1_1") (pintype "passive"))
      (node (ref "U3") (pin "143") (pinfunction "VDD_3_143") (pintype "power_in"))
    )
    (net (code "172") (name "Net-(RESET-0)") (class "Default")
      (node (ref "C9") (pin "2") (pinfunction "2_2") (pintype "passive"))
      (node (ref "RESET") (pin "P$1") (pinfunction "0_P$1") (pintype "passive"))
      (node (ref "R_RST1") (pin "1") (pinfunction "1_1") (pintype "passive"))
      (node (ref "R_RST2") (pin "2") (pinfunction "2_2") (pintype "passive"))
    )
    (net (code "173") (name "Net-(RM3B-1)") (class "Default")
      (node (ref "JTAG") (pin "17") (pinfunction "17_17") (pintype "passive"))
      (node (ref "RM3") (pin "2.1") (pinfunction "1_2.1") (pintype "passive"))
    )
    (net (code "174") (name "Net-(RM3C-1)") (class "Default")
      (node (ref "JTAG") (pin "11") (pinfunction "11_11") (pintype "passive"))
      (node (ref "R17") (pin "1") (pinfunction "1_1") (pintype "passive"))
      (node (ref "RM3") (pin "3.1") (pinfunction "1_3.1") (pintype "passive"))
    )
    (net (code "175") (name "Net-(RO-Pad1)") (class "Default")
      (node (ref "RO") (pin "1") (pinfunction "1_1") (pintype "passive"))
      (node (ref "U$5") (pin "A") (pinfunction "A_A") (pintype "passive"))
    )
    (net (code "176") (name "Net-(RR-Pad1)") (class "Default")
      (node (ref "RR") (pin "1") (pinfunction "1_1") (pintype "passive"))
      (node (ref "U$4") (pin "A") (pinfunction "A_A") (pintype "passive"))
    )
    (net (code "177") (name "Net-(RY-Pad1)") (class "Default")
      (node (ref "RY") (pin "1") (pinfunction "1_1") (pintype "passive"))
      (node (ref "U$3") (pin "A") (pinfunction "A_A") (pintype "passive"))
    )
    (net (code "178") (name "Net-(R_BALIN-Pad2)") (class "Default")
      (node (ref "R_BALIN") (pin "2") (pinfunction "2_2") (pintype "passive"))
      (node (ref "VOM_1271") (pin "1") (pinfunction "1_1") (pintype "bidirectional"))
    )
    (net (code "179") (name "Net-(T1-B)") (class "Default")
      (node (ref "R_TRAN") (pin "1") (pinfunction "1_1") (pintype "passive"))
      (node (ref "T1") (pin "2") (pinfunction "B_2") (pintype "passive"))
    )
    (net (code "180") (name "Net-(T1-C)") (class "Default")
      (node (ref "R_DISP") (pin "1") (pinfunction "1_1") (pintype "passive"))
      (node (ref "T1") (pin "3") (pinfunction "C_3") (pintype "passive"))
    )
    (net (code "181") (name "Net-(U$1-FB1)") (class "Default")
      (node (ref "C1P") (pin "2") (pinfunction "2_2") (pintype "passive"))
      (node (ref "R1_5V") (pin "1") (pinfunction "1_1") (pintype "passive"))
      (node (ref "R2_5V") (pin "2") (pinfunction "2_2") (pintype "passive"))
      (node (ref "U$1") (pin "9") (pinfunction "FB1_9") (pintype "bidirectional"))
    )
    (net (code "182") (name "Net-(U$1-FB2)") (class "Default")
      (node (ref "C3P") (pin "2") (pinfunction "2_2") (pintype "passive"))
      (node (ref "R1_3V3") (pin "1") (pinfunction "1_1") (pintype "passive"))
      (node (ref "R2_3V3") (pin "2") (pinfunction "2_2") (pintype "passive"))
      (node (ref "U$1") (pin "7") (pinfunction "FB2_7") (pintype "bidirectional"))
    )
    (net (code "183") (name "Net-(U$1-NR)") (class "Default")
      (node (ref "CNR") (pin "1") (pinfunction "1_1") (pintype "passive"))
      (node (ref "U$1") (pin "6") (pinfunction "NR_6") (pintype "bidirectional"))
    )
    (net (code "184") (name "Net-(U$8-DOUT)") (class "Default")
      (node (ref "HCPL092J-00E") (pin "IN4") (pinfunction "IN4_IN4") (pintype "bidirectional"))
      (node (ref "U$8") (pin "12") (pinfunction "DOUT_12") (pintype "output"))
    )
    (net (code "185") (name "Net-(U3-PB2{slash}BOOT1)") (class "Default")
      (node (ref "RBOOT2") (pin "1") (pinfunction "1_1") (pintype "passive"))
      (node (ref "U3") (pin "48") (pinfunction "PB2/BOOT1_48") (pintype "bidirectional"))
    )
    (net (code "186") (name "Net-(U3-PC15{slash}OSC32_OUT)") (class "Default")
      (node (ref "C7") (pin "1") (pinfunction "1_1") (pintype "passive"))
      (node (ref "Q2") (pin "1") (pinfunction "1_1") (pintype "passive"))
      (node (ref "R5") (pin "1") (pinfunction "1_1") (pintype "passive"))
      (node (ref "U3") (pin "9") (pinfunction "PC15/OSC32_OUT_9") (pintype "bidirectional"))
    )
    (net (code "187") (name "Net-(U3-PH0{slash}OSC_IN)") (class "Default")
      (node (ref "C25") (pin "1") (pinfunction "1_1") (pintype "passive"))
      (node (ref "Q1") (pin "1") (pinfunction "1_1") (pintype "passive"))
      (node (ref "R3") (pin "2") (pinfunction "2_2") (pintype "passive"))
      (node (ref "U3") (pin "23") (pinfunction "PH0/OSC_IN_23") (pintype "input"))
    )
    (net (code "188") (name "Net-(U3-PH1{slash}OSC_OUT)") (class "Default")
      (node (ref "R3") (pin "1") (pinfunction "1_1") (pintype "passive"))
      (node (ref "R_OSC") (pin "2") (pinfunction "2_2") (pintype "passive"))
      (node (ref "U3") (pin "24") (pinfunction "PH1/OSC_OUT_24") (pintype "output"))
    )
    (net (code "189") (name "Net-(U3-VCAP_1)") (class "Default")
      (node (ref "C23") (pin "2") (pinfunction "2_2") (pintype "passive"))
      (node (ref "U3") (pin "71") (pinfunction "VCAP_1_71") (pintype "output"))
    )
    (net (code "190") (name "Net-(U3-VCAP_2)") (class "Default")
      (node (ref "C24") (pin "2") (pinfunction "2_2") (pintype "passive"))
      (node (ref "U3") (pin "106") (pinfunction "VCAP_2_106") (pintype "output"))
    )
    (net (code "191") (name "Net-(U3-VREF+)") (class "Default")
      (node (ref "C6") (pin "2") (pinfunction "2_2") (pintype "passive"))
      (node (ref "R_REF") (pin "2") (pinfunction "2_2") (pintype "passive"))
      (node (ref "U3") (pin "32") (pinfunction "VREF+_32") (pintype "power_in"))
    )
    (net (code "192") (name "Net-(WKUP-1)") (class "Default")
      (node (ref "C29") (pin "1") (pinfunction "1_1") (pintype "passive"))
      (node (ref "RWK1") (pin "1") (pinfunction "1_1") (pintype "passive"))
      (node (ref "RWK2") (pin "2") (pinfunction "2_2") (pintype "passive"))
      (node (ref "WKUP") (pin "P$2") (pinfunction "1_P$2") (pintype "passive"))
    )
    (net (code "193") (name "unconnected-(BB_CON-Pad18)") (class "Default")
      (node (ref "BB_CON") (pin "18") (pinfunction "18_18") (pintype "passive"))
    )
    (net (code "194") (name "unconnected-(BB_CON-Pad19)") (class "Default")
      (node (ref "BB_CON") (pin "19") (pinfunction "19_19") (pintype "passive"))
    )
    (net (code "195") (name "unconnected-(BB_CON-Pad20)") (class "Default")
      (node (ref "BB_CON") (pin "20") (pinfunction "20_20") (pintype "passive"))
    )
    (net (code "196") (name "unconnected-(HCPL092J-00E-PadN1)") (class "Default")
      (node (ref "HCPL092J-00E") (pin "N1") (pinfunction "N1_N1") (pintype "bidirectional"))
    )
    (net (code "197") (name "unconnected-(HCPL092J-00E-PadN2)") (class "Default")
      (node (ref "HCPL092J-00E") (pin "N2") (pinfunction "N2_N2") (pintype "bidirectional"))
    )
    (net (code "198") (name "unconnected-(INA148-PadNC)") (class "Default")
      (node (ref "INA148") (pin "NC") (pinfunction "NC_NC") (pintype "bidirectional"))
    )
    (net (code "199") (name "unconnected-(INA148-PadNC1)") (class "Default")
      (node (ref "INA148") (pin "NC1") (pinfunction "NC1_NC1") (pintype "bidirectional"))
    )
    (net (code "200") (name "unconnected-(LEFT_COMM-Pad10)") (class "Default")
      (node (ref "LEFT_COMM") (pin "10") (pinfunction "10_10") (pintype "passive"))
    )
    (net (code "201") (name "unconnected-(LEFT_TX-Pad1)") (class "Default")
      (node (ref "LEFT_TX") (pin "1") (pinfunction "1_1") (pintype "passive"))
    )
    (net (code "202") (name "unconnected-(LEFT_TX-Pad5)") (class "Default")
      (node (ref "LEFT_TX") (pin "5") (pinfunction "5_5") (pintype "passive"))
    )
    (net (code "203") (name "unconnected-(PF-Pad19)") (class "Default")
      (node (ref "PF") (pin "19") (pinfunction "19_19") (pintype "passive"))
    )
    (net (code "204") (name "unconnected-(PF-Pad20)") (class "Default")
      (node (ref "PF") (pin "20") (pinfunction "20_20") (pintype "passive"))
    )
    (net (code "205") (name "unconnected-(PG-Pad11)") (class "Default")
      (node (ref "PG") (pin "11") (pinfunction "11_11") (pintype "passive"))
    )
    (net (code "206") (name "unconnected-(PG-Pad19)") (class "Default")
      (node (ref "PG") (pin "19") (pinfunction "19_19") (pintype "passive"))
    )
    (net (code "207") (name "unconnected-(PG-Pad20)") (class "Default")
      (node (ref "PG") (pin "20") (pinfunction "20_20") (pintype "passive"))
    )
    (net (code "208") (name "unconnected-(RIGHT_COMM-Pad10)") (class "Default")
      (node (ref "RIGHT_COMM") (pin "10") (pinfunction "10_10") (pintype "passive"))
    )
    (net (code "209") (name "unconnected-(RIGHT_TX1-Pad1)") (class "Default")
      (node (ref "RIGHT_TX1") (pin "1") (pinfunction "1_1") (pintype "passive"))
    )
    (net (code "210") (name "unconnected-(RIGHT_TX1-Pad5)") (class "Default")
      (node (ref "RIGHT_TX1") (pin "5") (pinfunction "5_5") (pintype "passive"))
    )
    (net (code "211") (name "unconnected-(U$1-NC-Pad2)") (class "Default")
      (node (ref "U$1") (pin "2") (pinfunction "NC_2") (pintype "bidirectional"))
    )
    (net (code "212") (name "unconnected-(U$2-PadDNC1)") (class "Default")
      (node (ref "U$2") (pin "DNC1") (pinfunction "DNC1_DNC1") (pintype "bidirectional"))
    )
    (net (code "213") (name "unconnected-(U$2-PadDNC8)") (class "Default")
      (node (ref "U$2") (pin "DNC8") (pinfunction "DNC8_DNC8") (pintype "bidirectional"))
    )
    (net (code "214") (name "unconnected-(U$2-PadNC)") (class "Default")
      (node (ref "U$2") (pin "NC") (pinfunction "NC_NC") (pintype "bidirectional"))
    )
    (net (code "215") (name "unconnected-(U$2-PadTEMP)") (class "Default")
      (node (ref "U$2") (pin "TEMP") (pinfunction "TEMP_TEMP") (pintype "bidirectional"))
    )
    (net (code "216") (name "unconnected-(U$8-BUSY-Pad13)") (class "Default")
      (node (ref "U$8") (pin "13") (pinfunction "BUSY_13") (pintype "output"))
    )
    (net (code "217") (name "unconnected-(U1-NC-Pad2)") (class "Default")
      (node (ref "U1") (pin "2") (pinfunction "NC_2") (pintype "passive"))
    )
    (net (code "218") (name "unconnected-(U1-VREF-Pad14)") (class "Default")
      (node (ref "U1") (pin "14") (pinfunction "VREF_14") (pintype "passive"))
    )
    (net (code "219") (name "unconnected-(U3-PE13{slash}FSMC_D10{slash}TIM1_CH3-Pad66)") (class "Default")
      (node (ref "U3") (pin "66") (pinfunction "PE13/FSMC_D10/TIM1_CH3_66") (pintype "bidirectional"))
    )
  )
)
